# dc26.net
KiCad netlist of a schematic drawn in EAGLE
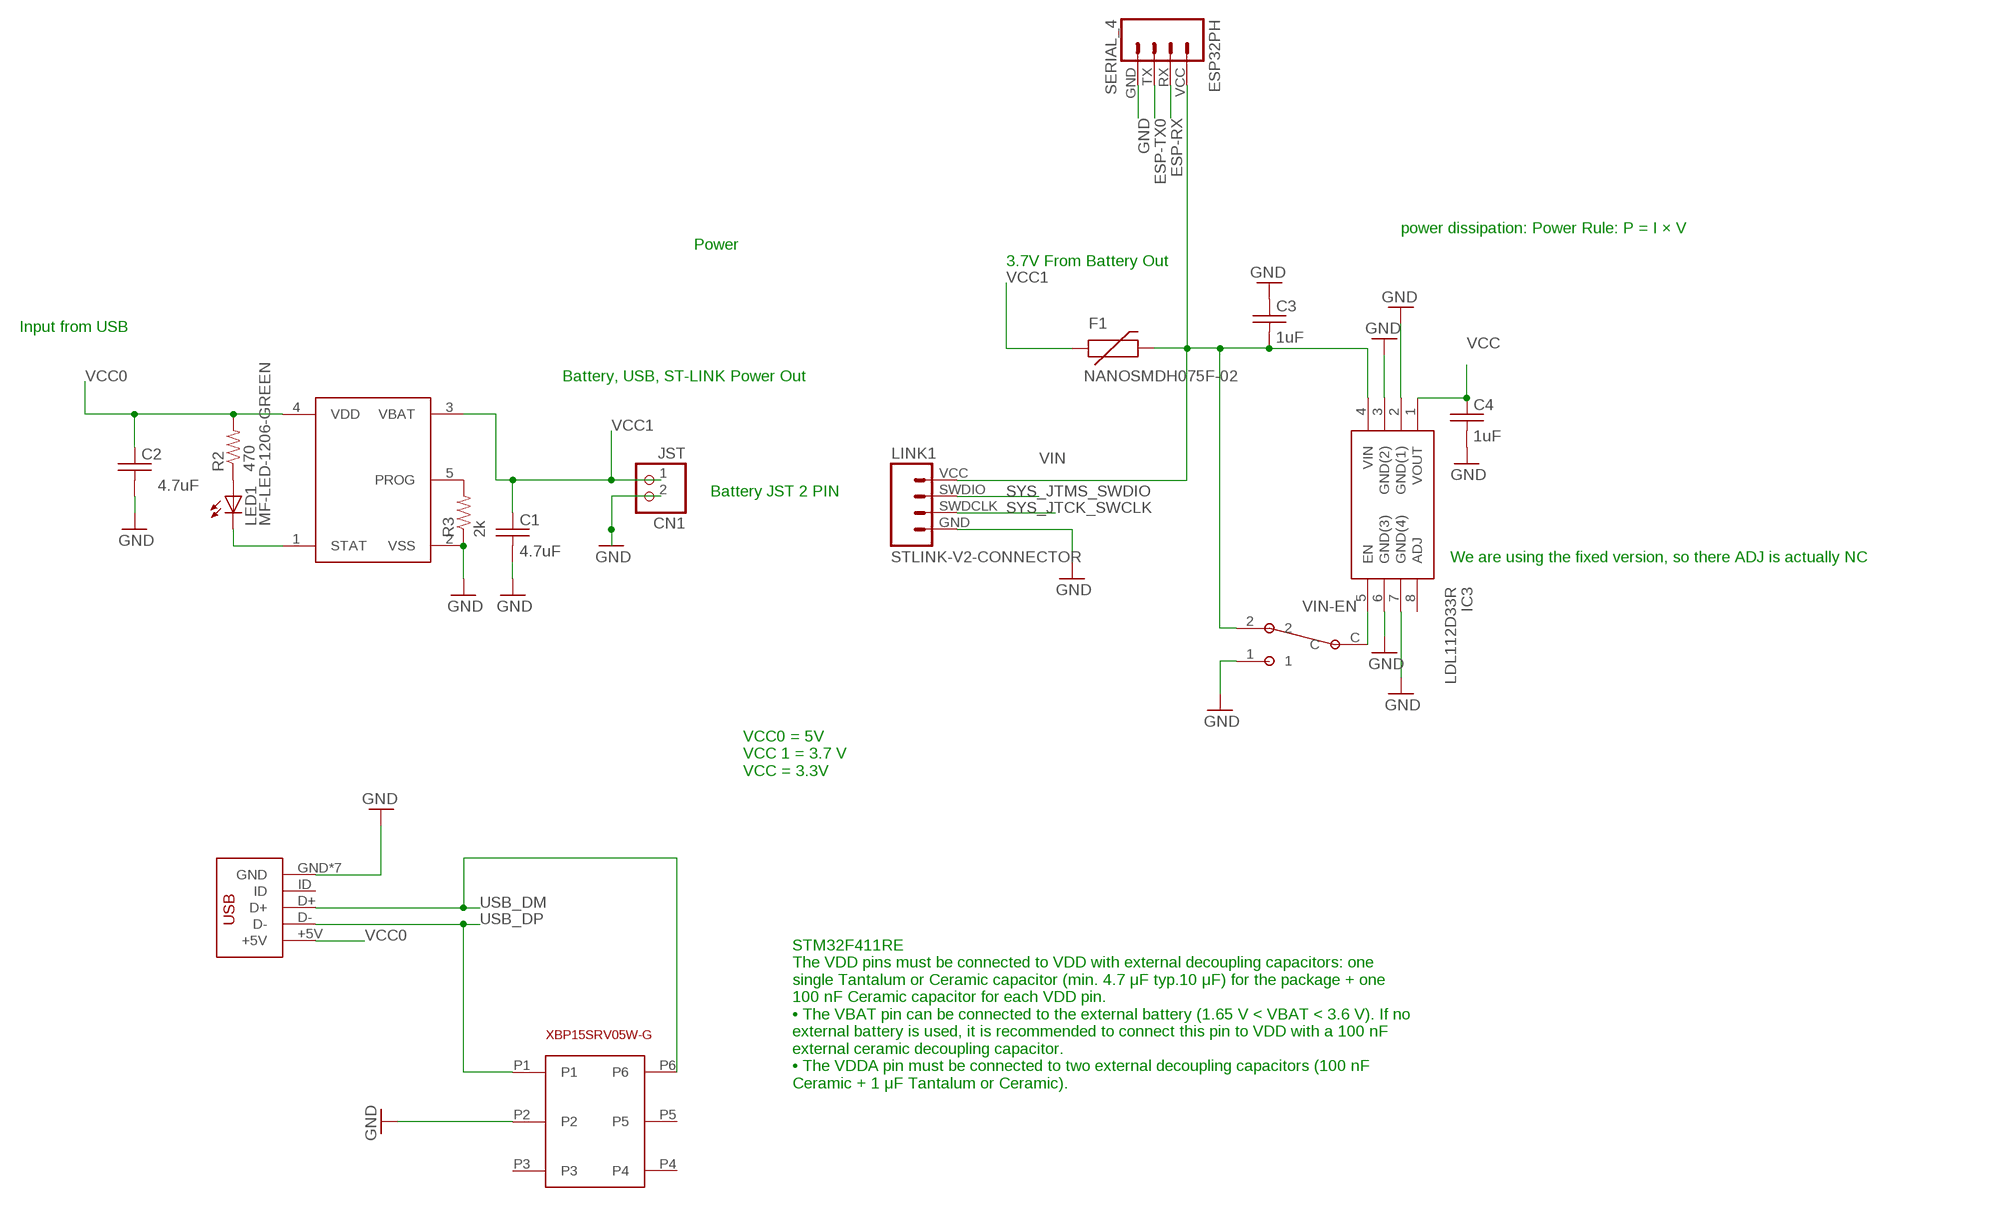
[diagram p0: schematic, sheet 1]
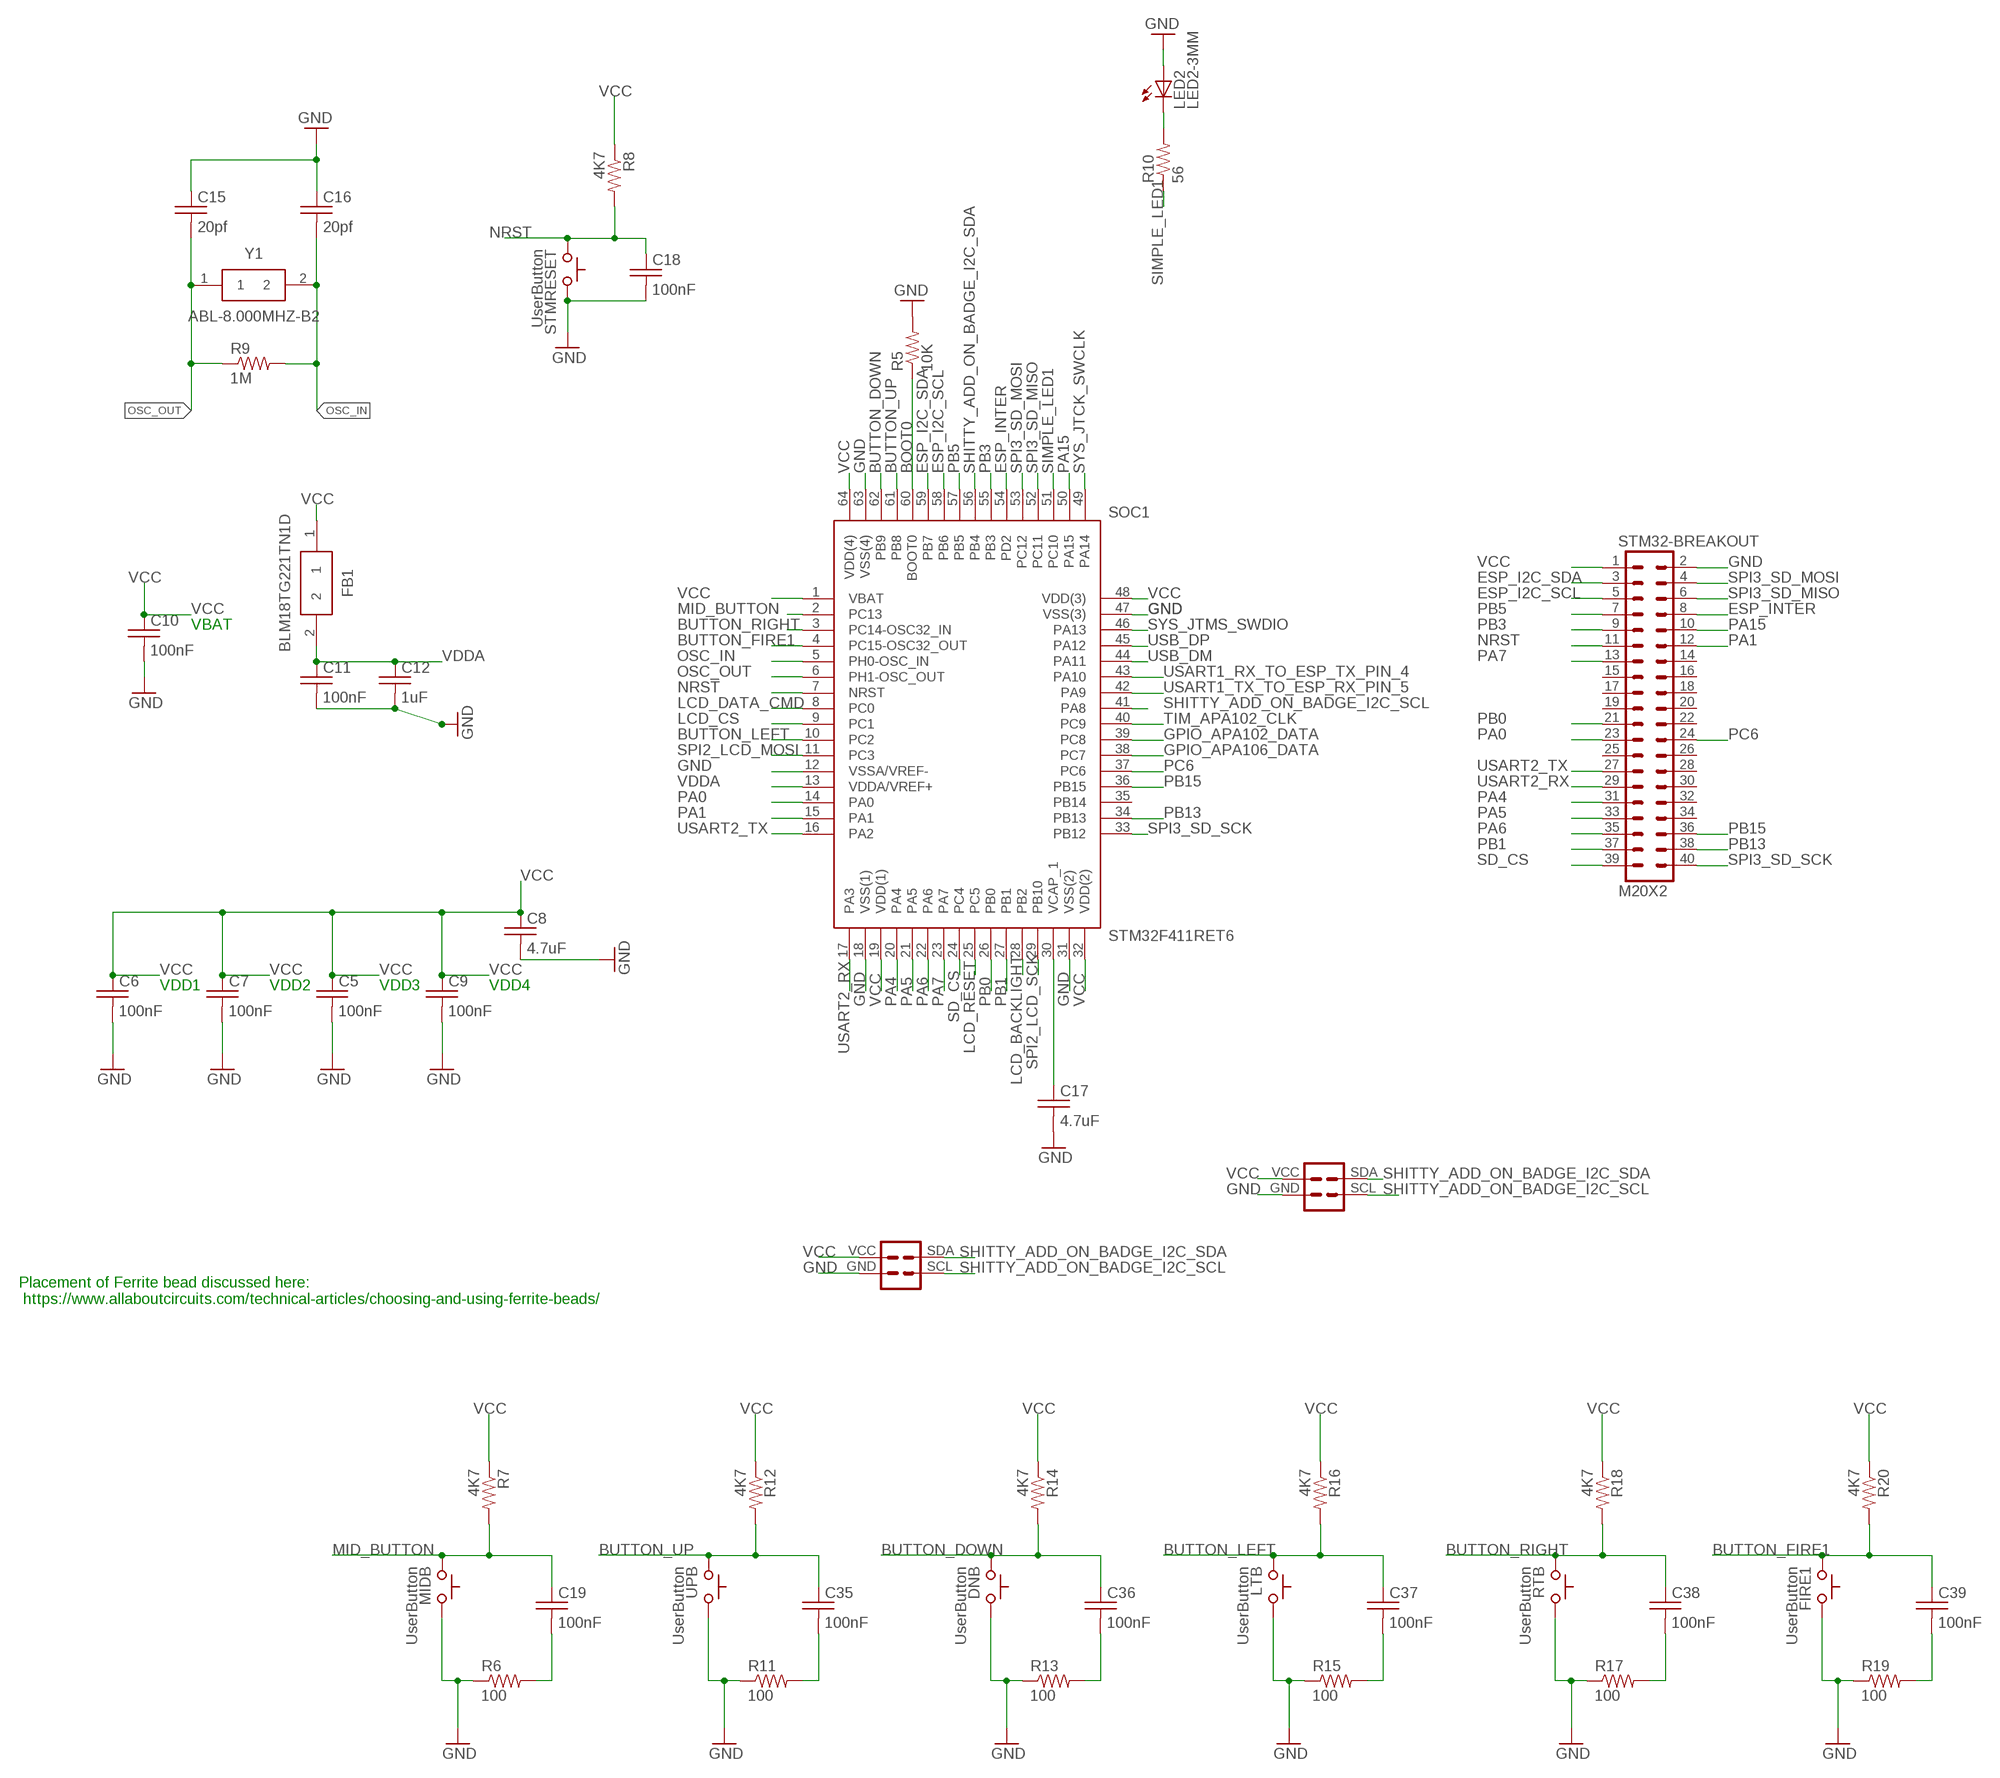
[diagram p1: schematic, sheet 2]
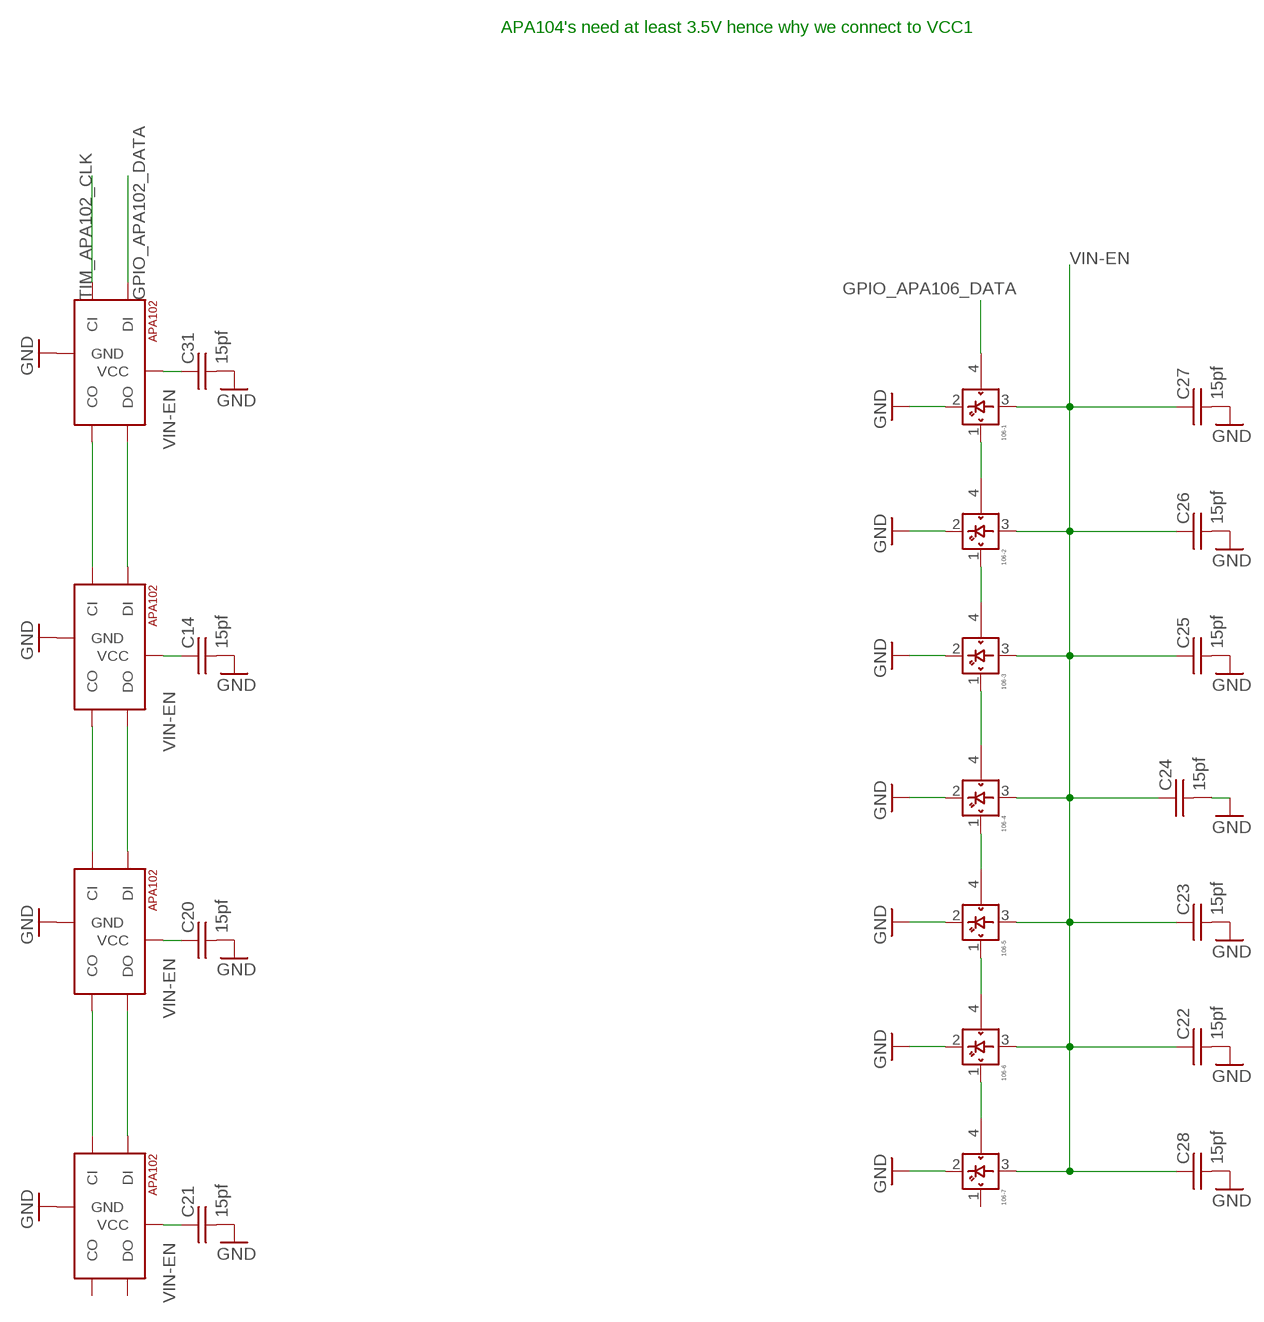
[diagram p2: schematic, sheet 3]
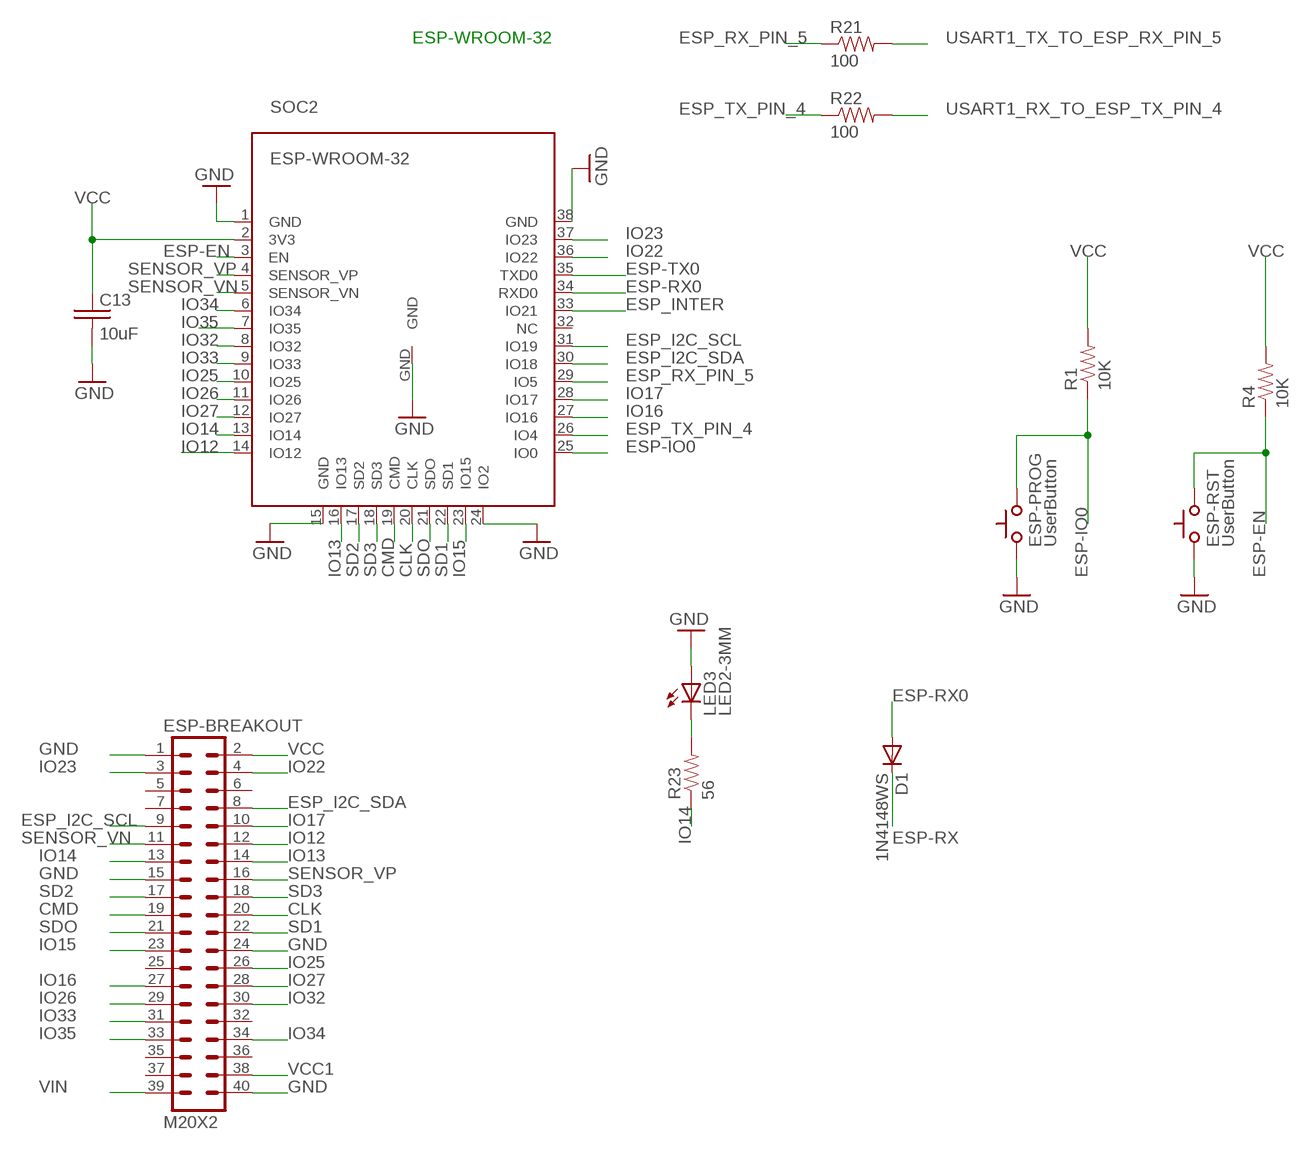
[diagram p3: schematic, sheet 4]
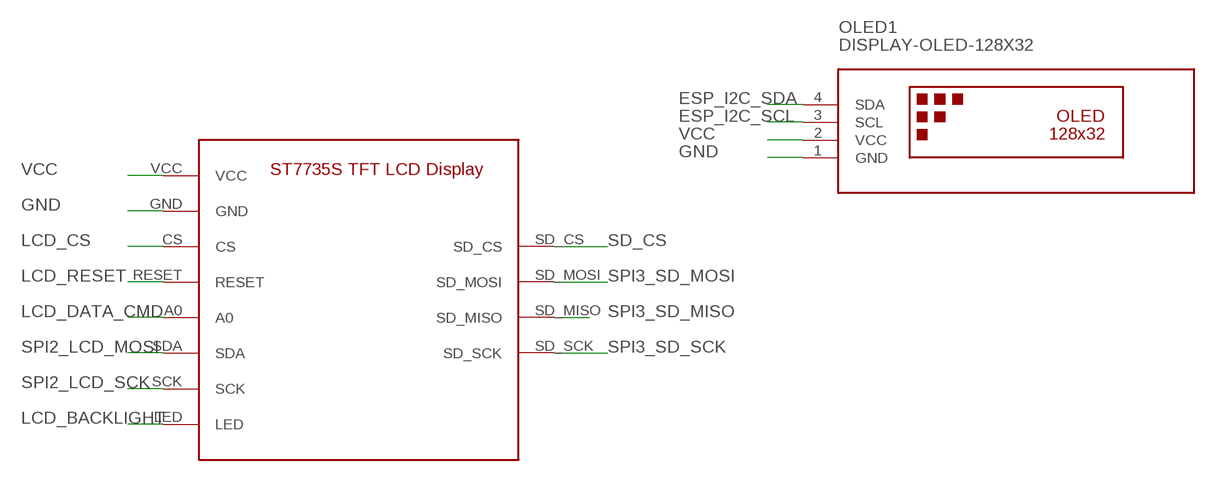
[diagram p4: schematic, sheet 5]
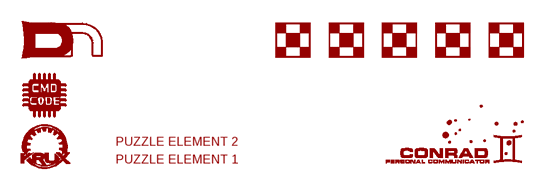
[diagram p5: schematic, sheet 6]
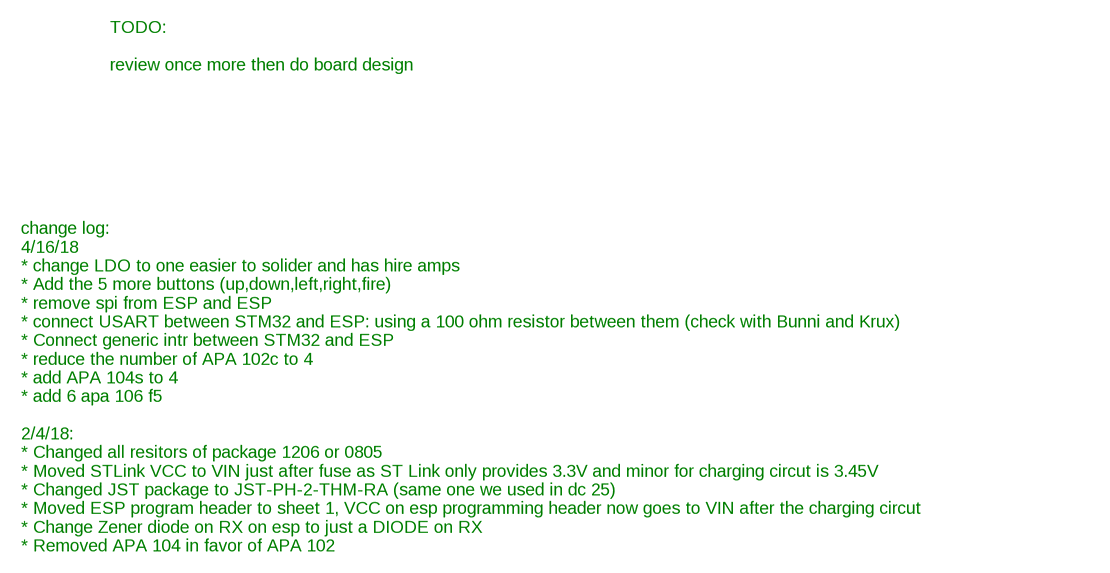
[diagram p6: schematic, sheet 7]

(export (version "E")
  (design (tool "Eeschema 10.0.6"))
  (components
    (comp (ref "C5")
      (value "100nF")
      (footprint "eagle-import:C0805")
      (libsource (lib "eagle-import") (part "C-USC0805"))
    )
    (comp (ref "C6")
      (value "100nF")
      (footprint "eagle-import:C0805")
      (libsource (lib "eagle-import") (part "C-USC0805"))
    )
    (comp (ref "C7")
      (value "100nF")
      (footprint "eagle-import:C0805")
      (libsource (lib "eagle-import") (part "C-USC0805"))
    )
    (comp (ref "C8")
      (value "4.7uF")
      (footprint "eagle-import:C0805")
      (libsource (lib "eagle-import") (part "C-USC0805"))
    )
    (comp (ref "C9")
      (value "100nF")
      (footprint "eagle-import:C0805")
      (libsource (lib "eagle-import") (part "C-USC0805"))
    )
    (comp (ref "C10")
      (value "100nF")
      (footprint "eagle-import:C0805")
      (libsource (lib "eagle-import") (part "C-USC0805"))
    )
    (comp (ref "C11")
      (value "100nF")
      (footprint "eagle-import:C0805")
      (libsource (lib "eagle-import") (part "C-USC0805"))
    )
    (comp (ref "C12")
      (value "1uF")
      (footprint "eagle-import:C0805")
      (libsource (lib "eagle-import") (part "C-USC0805"))
    )
    (comp (ref "C15")
      (value "20pf")
      (footprint "eagle-import:C0805")
      (libsource (lib "eagle-import") (part "C-USC0805"))
    )
    (comp (ref "C16")
      (value "20pf")
      (footprint "eagle-import:C0805")
      (libsource (lib "eagle-import") (part "C-USC0805"))
    )
    (comp (ref "C17")
      (value "4.7uF")
      (footprint "eagle-import:C0805")
      (libsource (lib "eagle-import") (part "C-USC0805"))
    )
    (comp (ref "C18")
      (value "100nF")
      (footprint "eagle-import:C0805")
      (libsource (lib "eagle-import") (part "C-USC0805"))
    )
    (comp (ref "C19")
      (value "100nF")
      (footprint "eagle-import:C0805")
      (libsource (lib "eagle-import") (part "C-USC0805"))
    )
    (comp (ref "C35")
      (value "100nF")
      (footprint "eagle-import:C0805")
      (libsource (lib "eagle-import") (part "C-USC0805"))
    )
    (comp (ref "C36")
      (value "100nF")
      (footprint "eagle-import:C0805")
      (libsource (lib "eagle-import") (part "C-USC0805"))
    )
    (comp (ref "C37")
      (value "100nF")
      (footprint "eagle-import:C0805")
      (libsource (lib "eagle-import") (part "C-USC0805"))
    )
    (comp (ref "C38")
      (value "100nF")
      (footprint "eagle-import:C0805")
      (libsource (lib "eagle-import") (part "C-USC0805"))
    )
    (comp (ref "C39")
      (value "100nF")
      (footprint "eagle-import:C0805")
      (libsource (lib "eagle-import") (part "C-USC0805"))
    )
    (comp (ref "DNB")
      (value "UserButton")
      (footprint "eagle-import:TACTILE-2PIN-NARROW")
      (libsource (lib "eagle-import") (part "SWITCH_TACTILETACTILE-2PIN-NARROW"))
    )
    (comp (ref "FB1")
      (value "BLM18TG221TN1D")
      (footprint "eagle-import:BEADC1608X75N")
      (fields (field (name "RS_PART_NUMBER") "6197526"))
      (libsource (lib "eagle-import") (part "BLM18TG221TN1D"))
    )
    (comp (ref "FIRE1")
      (value "UserButton")
      (footprint "eagle-import:TACTILE-2PIN-NARROW")
      (libsource (lib "eagle-import") (part "SWITCH_TACTILETACTILE-2PIN-NARROW"))
    )
    (comp (ref "J1")
      (value "DC26 Shitty AddOn")
      (footprint "eagle-import:DC26SHITTY_ADDON_CONNECTOR")
      (libsource (lib "eagle-import") (part "DC26_SHITTY_ADDON_CONNECTORPTH"))
    )
    (comp (ref "J2")
      (value "DC26 Shitty AddOn")
      (footprint "eagle-import:DC26SHITTY_ADDON_CONNECTOR")
      (libsource (lib "eagle-import") (part "DC26_SHITTY_ADDON_CONNECTORPTH"))
    )
    (comp (ref "LED2")
      (value "LED2-3MM")
      (footprint "eagle-import:LED3MM")
      (libsource (lib "eagle-import") (part "LED3MM"))
    )
    (comp (ref "LTB")
      (value "UserButton")
      (footprint "eagle-import:TACTILE-2PIN-NARROW")
      (libsource (lib "eagle-import") (part "SWITCH_TACTILETACTILE-2PIN-NARROW"))
    )
    (comp (ref "MIDB")
      (value "UserButton")
      (footprint "eagle-import:TACTILE-2PIN-NARROW")
      (libsource (lib "eagle-import") (part "SWITCH_TACTILETACTILE-2PIN-NARROW"))
    )
    (comp (ref "R5")
      (value "10K")
      (footprint "eagle-import:0805")
      (libsource (lib "eagle-import") (part "RESISTOR0805-RES"))
    )
    (comp (ref "R6")
      (value "100")
      (footprint "eagle-import:0805")
      (libsource (lib "eagle-import") (part "RESISTOR0805-RES"))
    )
    (comp (ref "R7")
      (value "4K7")
      (footprint "eagle-import:0805")
      (libsource (lib "eagle-import") (part "RESISTOR0805-RES"))
    )
    (comp (ref "R8")
      (value "4K7")
      (footprint "eagle-import:0805")
      (libsource (lib "eagle-import") (part "RESISTOR0805-RES"))
    )
    (comp (ref "R9")
      (value "1M")
      (footprint "eagle-import:0805")
      (libsource (lib "eagle-import") (part "RESISTOR0805-RES"))
    )
    (comp (ref "R10")
      (value "56")
      (footprint "eagle-import:0805")
      (libsource (lib "eagle-import") (part "RESISTOR0805-RES"))
    )
    (comp (ref "R11")
      (value "100")
      (footprint "eagle-import:0805")
      (libsource (lib "eagle-import") (part "RESISTOR0805-RES"))
    )
    (comp (ref "R12")
      (value "4K7")
      (footprint "eagle-import:0805")
      (libsource (lib "eagle-import") (part "RESISTOR0805-RES"))
    )
    (comp (ref "R13")
      (value "100")
      (footprint "eagle-import:0805")
      (libsource (lib "eagle-import") (part "RESISTOR0805-RES"))
    )
    (comp (ref "R14")
      (value "4K7")
      (footprint "eagle-import:0805")
      (libsource (lib "eagle-import") (part "RESISTOR0805-RES"))
    )
    (comp (ref "R15")
      (value "100")
      (footprint "eagle-import:0805")
      (libsource (lib "eagle-import") (part "RESISTOR0805-RES"))
    )
    (comp (ref "R16")
      (value "4K7")
      (footprint "eagle-import:0805")
      (libsource (lib "eagle-import") (part "RESISTOR0805-RES"))
    )
    (comp (ref "R17")
      (value "100")
      (footprint "eagle-import:0805")
      (libsource (lib "eagle-import") (part "RESISTOR0805-RES"))
    )
    (comp (ref "R18")
      (value "4K7")
      (footprint "eagle-import:0805")
      (libsource (lib "eagle-import") (part "RESISTOR0805-RES"))
    )
    (comp (ref "R19")
      (value "100")
      (footprint "eagle-import:0805")
      (libsource (lib "eagle-import") (part "RESISTOR0805-RES"))
    )
    (comp (ref "R20")
      (value "4K7")
      (footprint "eagle-import:0805")
      (libsource (lib "eagle-import") (part "RESISTOR0805-RES"))
    )
    (comp (ref "RTB")
      (value "UserButton")
      (footprint "eagle-import:TACTILE-2PIN-NARROW")
      (libsource (lib "eagle-import") (part "SWITCH_TACTILETACTILE-2PIN-NARROW"))
    )
    (comp (ref "SOC1")
      (value "STM32F411RET6")
      (footprint "eagle-import:QFP50P1200X1200X160-64N")
      (fields (field (name "RS_PART_NUMBER") "1106617P"))
      (libsource (lib "eagle-import") (part "STM32F411RET6"))
    )
    (comp (ref "STM32-BREAKOUT")
      (value "M20X2")
      (footprint "eagle-import:2X20")
      (libsource (lib "eagle-import") (part "M20X2"))
    )
    (comp (ref "STMRESET")
      (value "UserButton")
      (footprint "eagle-import:TACTILE-2PIN-NARROW")
      (libsource (lib "eagle-import") (part "SWITCH_TACTILETACTILE-2PIN-NARROW"))
    )
    (comp (ref "UPB")
      (value "UserButton")
      (footprint "eagle-import:TACTILE-2PIN-NARROW")
      (libsource (lib "eagle-import") (part "SWITCH_TACTILETACTILE-2PIN-NARROW"))
    )
    (comp (ref "Y1")
      (value "ABL-8.000MHZ-B2")
      (footprint "eagle-import:HC_49US_(AT49)PTH")
      (libsource (lib "eagle-import") (part "ABL-8.000MHZ-B2"))
    )
    (comp (ref "C13")
      (value "10uF")
      (footprint "eagle-import:C0805")
      (libsource (lib "eagle-import") (part "C-USC0805"))
    )
    (comp (ref "D1")
      (value "1N4148WS")
      (footprint "eagle-import:SOD-323")
      (libsource (lib "eagle-import") (part "DIODESOD"))
    )
    (comp (ref "ESP-BREAKOUT")
      (value "M20X2")
      (footprint "eagle-import:2X20")
      (libsource (lib "eagle-import") (part "M20X2"))
    )
    (comp (ref "ESP-PROG")
      (value "UserButton")
      (footprint "eagle-import:TACTILE-2PIN-NARROW")
      (libsource (lib "eagle-import") (part "SWITCH_TACTILETACTILE-2PIN-NARROW"))
    )
    (comp (ref "ESP-RST")
      (value "UserButton")
      (footprint "eagle-import:TACTILE-2PIN-NARROW")
      (libsource (lib "eagle-import") (part "SWITCH_TACTILETACTILE-2PIN-NARROW"))
    )
    (comp (ref "LED3")
      (value "LED2-3MM")
      (footprint "eagle-import:LED3MM")
      (libsource (lib "eagle-import") (part "LED3MM"))
    )
    (comp (ref "R1")
      (value "10K")
      (footprint "eagle-import:0805")
      (libsource (lib "eagle-import") (part "RESISTOR0805-RES"))
    )
    (comp (ref "R4")
      (value "10K")
      (footprint "eagle-import:0805")
      (libsource (lib "eagle-import") (part "RESISTOR0805-RES"))
    )
    (comp (ref "R21")
      (value "100")
      (footprint "eagle-import:0805")
      (libsource (lib "eagle-import") (part "RESISTOR0805-RES"))
    )
    (comp (ref "R22")
      (value "100")
      (footprint "eagle-import:0805")
      (libsource (lib "eagle-import") (part "RESISTOR0805-RES"))
    )
    (comp (ref "R23")
      (value "56")
      (footprint "eagle-import:0805")
      (libsource (lib "eagle-import") (part "RESISTOR0805-RES"))
    )
    (comp (ref "SOC2")
      (value "ESP-WROOM-32")
      (footprint "eagle-import:ESP-WROOM-32")
      (libsource (lib "eagle-import") (part "ESP-WROOM-32"))
    )
    (comp (ref "C1")
      (value "4.7uF")
      (footprint "eagle-import:C0805")
      (libsource (lib "eagle-import") (part "C-USC0805"))
    )
    (comp (ref "C2")
      (value "4.7uF")
      (footprint "eagle-import:C0805")
      (libsource (lib "eagle-import") (part "C-USC0805"))
    )
    (comp (ref "C3")
      (value "1uF")
      (footprint "eagle-import:C0805")
      (libsource (lib "eagle-import") (part "C-USC0805"))
    )
    (comp (ref "C4")
      (value "1uF")
      (footprint "eagle-import:C0805")
      (libsource (lib "eagle-import") (part "C-USC0805"))
    )
    (comp (ref "CHARGE")
      (value "MCP73831")
      (footprint "eagle-import:SOT23-5")
      (libsource (lib "eagle-import") (part "DS21984E"))
    )
    (comp (ref "CN1")
      (value "JST")
      (footprint "eagle-import:JST-PH-2-THM-RA")
      (libsource (lib "eagle-import") (part "JST_2PIN-THM-RA"))
    )
    (comp (ref "ESP32PH")
      (value "SERIAL_4")
      (footprint "eagle-import:SERIAL_HEADER_4")
      (libsource (lib "eagle-import") (part "SERIAL_4"))
    )
    (comp (ref "F1")
      (value "NANOSMDH075F-02")
      (footprint "eagle-import:PTC-1206")
      (libsource (lib "eagle-import") (part "PTCSMD"))
    )
    (comp (ref "IC3")
      (value "LDL112D33R")
      (footprint "eagle-import:SOIC127P600X175-8N")
      (libsource (lib "eagle-import") (part "LDL112D33R"))
    )
    (comp (ref "LED1")
      (value "MF-LED-1206-GREEN")
      (footprint "eagle-import:LED-1206")
      (libsource (lib "eagle-import") (part "LED1206"))
    )
    (comp (ref "LINK1")
      (value "STLINK-V2-CONNECTOR")
      (footprint "eagle-import:1X04")
      (libsource (lib "eagle-import") (part "STLINK-V2-CONNECTOR"))
    )
    (comp (ref "P1")
      (value "SPDT_SSAJ120100")
      (footprint "eagle-import:SPDT_SSAJ120100")
      (libsource (lib "eagle-import") (part "SWITCH_SPDT"))
    )
    (comp (ref "R2")
      (value "470")
      (footprint "eagle-import:0805")
      (libsource (lib "eagle-import") (part "RESISTOR0805-RES"))
    )
    (comp (ref "R3")
      (value "2k")
      (footprint "eagle-import:0805")
      (libsource (lib "eagle-import") (part "RESISTOR0805-RES"))
    )
    (comp (ref "U$17")
      (value "XBP15SRV05W-G")
      (footprint "eagle-import:SOT-26P-XBP15SRV05W-G")
      (fields (field (name "DIGI_KEY_PART_NUMBER") "893-1422-1-ND"))
      (libsource (lib "eagle-import") (part "XBP15SRV05W-G"))
    )
    (comp (ref "USB")
      (value "DX4R005JJ2DX4R005JJ2")
      (footprint "eagle-import:DX4R005JJ2")
      (libsource (lib "eagle-import") (part "DX4R005JJ2DX4R005JJ2"))
    )
    (comp (ref "102-1")
      (value "APA1025050")
      (footprint "eagle-import:APA102_5050")
      (libsource (lib "eagle-import") (part "APA1025050"))
    )
    (comp (ref "102-2")
      (value "APA1025050")
      (footprint "eagle-import:APA102_5050")
      (libsource (lib "eagle-import") (part "APA1025050"))
    )
    (comp (ref "102-3")
      (value "APA1025050")
      (footprint "eagle-import:APA102_5050")
      (libsource (lib "eagle-import") (part "APA1025050"))
    )
    (comp (ref "102-4")
      (value "APA1025050")
      (footprint "eagle-import:APA102_5050")
      (libsource (lib "eagle-import") (part "APA1025050"))
    )
    (comp (ref "106-1")
      (value "APA-106")
      (footprint "eagle-import:WS2812F5_STRAIGHT")
      (libsource (lib "eagle-import") (part "APA-106"))
    )
    (comp (ref "106-2")
      (value "APA-106")
      (footprint "eagle-import:WS2812F5_STRAIGHT")
      (libsource (lib "eagle-import") (part "APA-106"))
    )
    (comp (ref "106-3")
      (value "APA-106")
      (footprint "eagle-import:WS2812F5_STRAIGHT")
      (libsource (lib "eagle-import") (part "APA-106"))
    )
    (comp (ref "106-4")
      (value "APA-106")
      (footprint "eagle-import:WS2812F5_STRAIGHT")
      (libsource (lib "eagle-import") (part "APA-106"))
    )
    (comp (ref "106-5")
      (value "APA-106")
      (footprint "eagle-import:WS2812F5_STRAIGHT")
      (libsource (lib "eagle-import") (part "APA-106"))
    )
    (comp (ref "106-6")
      (value "APA-106")
      (footprint "eagle-import:WS2812F5_STRAIGHT")
      (libsource (lib "eagle-import") (part "APA-106"))
    )
    (comp (ref "106-7")
      (value "APA-106")
      (footprint "eagle-import:WS2812F5_STRAIGHT")
      (libsource (lib "eagle-import") (part "APA-106"))
    )
    (comp (ref "C14")
      (value "15pf")
      (footprint "eagle-import:C0805")
      (libsource (lib "eagle-import") (part "C-USC0805"))
    )
    (comp (ref "C20")
      (value "15pf")
      (footprint "eagle-import:C0805")
      (libsource (lib "eagle-import") (part "C-USC0805"))
    )
    (comp (ref "C21")
      (value "15pf")
      (footprint "eagle-import:C0805")
      (libsource (lib "eagle-import") (part "C-USC0805"))
    )
    (comp (ref "C22")
      (value "15pf")
      (footprint "eagle-import:C0805")
      (libsource (lib "eagle-import") (part "C-USC0805"))
    )
    (comp (ref "C23")
      (value "15pf")
      (footprint "eagle-import:C0805")
      (libsource (lib "eagle-import") (part "C-USC0805"))
    )
    (comp (ref "C24")
      (value "15pf")
      (footprint "eagle-import:C0805")
      (libsource (lib "eagle-import") (part "C-USC0805"))
    )
    (comp (ref "C25")
      (value "15pf")
      (footprint "eagle-import:C0805")
      (libsource (lib "eagle-import") (part "C-USC0805"))
    )
    (comp (ref "C26")
      (value "15pf")
      (footprint "eagle-import:C0805")
      (libsource (lib "eagle-import") (part "C-USC0805"))
    )
    (comp (ref "C27")
      (value "15pf")
      (footprint "eagle-import:C0805")
      (libsource (lib "eagle-import") (part "C-USC0805"))
    )
    (comp (ref "C28")
      (value "15pf")
      (footprint "eagle-import:C0805")
      (libsource (lib "eagle-import") (part "C-USC0805"))
    )
    (comp (ref "C31")
      (value "15pf")
      (footprint "eagle-import:C0805")
      (libsource (lib "eagle-import") (part "C-USC0805"))
    )
    (comp (ref "LCD1")
      (value "ST7735S_LCD_MODULE")
      (footprint "eagle-import:ST7735S_LCD_DISPLAY")
      (libsource (lib "eagle-import") (part "ST7735S_LCD_MODULE"))
    )
    (comp (ref "OLED1")
      (value "DISPLAY-OLED-128X32")
      (footprint "eagle-import:DISPLAY-OLED-128X32")
      (libsource (lib "eagle-import") (part "DISPLAY-OLED-128X32"))
    )
    (comp (ref "U$1")
      (value "KRUX_LOGO")
      (footprint "eagle-import:KRUX_LOGO")
      (libsource (lib "eagle-import") (part "KRUX_LOGO"))
    )
    (comp (ref "U$2")
      (value "CMD_C0DE_LOGO")
      (footprint "eagle-import:CMD_C0DE_LOGO")
      (libsource (lib "eagle-import") (part "CMD_C0DE_LOGO"))
    )
    (comp (ref "U$3")
      (value "DC26_KRUX_PUZZLE_1")
      (footprint "eagle-import:DN26_KRUX_PUZZLE_1")
      (libsource (lib "eagle-import") (part "DC26_KRUX_PUZZLE_1"))
    )
    (comp (ref "U$4")
      (value "DC26_KRUX_PUZZLE_2")
      (footprint "eagle-import:DN26_KRUX_PUZZLE_2")
      (libsource (lib "eagle-import") (part "DC26_KRUX_PUZZLE_2"))
    )
    (comp (ref "U$5")
      (value "CONRAD_LOGO")
      (footprint "eagle-import:CONRAD_LOGO")
      (libsource (lib "eagle-import") (part "CONRAD_LOGO"))
    )
    (comp (ref "U$6")
      (value "DN_LOGODC26")
      (footprint "eagle-import:DN_LOGO_DC26")
      (libsource (lib "eagle-import") (part "DN_LOGODC26"))
    )
    (comp (ref "U$7")
      (value "FIDUCIAL_DNBOX")
      (footprint "eagle-import:FIDUCIAL_BOX")
      (libsource (lib "eagle-import") (part "FIDUCIAL_DNBOX"))
    )
    (comp (ref "U$8")
      (value "FIDUCIAL_DNBOX")
      (footprint "eagle-import:FIDUCIAL_BOX")
      (libsource (lib "eagle-import") (part "FIDUCIAL_DNBOX"))
    )
    (comp (ref "U$9")
      (value "FIDUCIAL_DNCORNER")
      (footprint "eagle-import:FIDUCIAL_CORNER")
      (libsource (lib "eagle-import") (part "FIDUCIAL_DNCORNER"))
    )
    (comp (ref "U$10")
      (value "FIDUCIAL_DNCORNER")
      (footprint "eagle-import:FIDUCIAL_CORNER")
      (libsource (lib "eagle-import") (part "FIDUCIAL_DNCORNER"))
    )
    (comp (ref "U$11")
      (value "FIDUCIAL_DNCORNER")
      (footprint "eagle-import:FIDUCIAL_CORNER")
      (libsource (lib "eagle-import") (part "FIDUCIAL_DNCORNER"))
    )
  )
  (nets
    (net (code "1") (name "BOOT0") (class "Default")
      (node (ref "R5") (pin "1") (pinfunction "1_1") (pintype "passive"))
      (node (ref "SOC1") (pin "60") (pinfunction "BOOT0_60") (pintype "passive"))
    )
    (net (code "2") (name "BUTTON_DOWN") (class "Default")
      (node (ref "C36") (pin "1") (pinfunction "1_1") (pintype "passive"))
      (node (ref "DNB") (pin "P$2") (pinfunction "C_P$2") (pintype "passive"))
      (node (ref "R14") (pin "2") (pinfunction "2_2") (pintype "passive"))
      (node (ref "SOC1") (pin "62") (pinfunction "PB9_62") (pintype "passive"))
    )
    (net (code "3") (name "BUTTON_FIRE1") (class "Default")
      (node (ref "C39") (pin "1") (pinfunction "1_1") (pintype "passive"))
      (node (ref "FIRE1") (pin "P$2") (pinfunction "C_P$2") (pintype "passive"))
      (node (ref "R20") (pin "2") (pinfunction "2_2") (pintype "passive"))
      (node (ref "SOC1") (pin "4") (pinfunction "PC15-OSC32_OUT_4") (pintype "passive"))
    )
    (net (code "4") (name "BUTTON_LEFT") (class "Default")
      (node (ref "C37") (pin "1") (pinfunction "1_1") (pintype "passive"))
      (node (ref "LTB") (pin "P$2") (pinfunction "C_P$2") (pintype "passive"))
      (node (ref "R16") (pin "2") (pinfunction "2_2") (pintype "passive"))
      (node (ref "SOC1") (pin "10") (pinfunction "PC2_10") (pintype "passive"))
    )
    (net (code "5") (name "BUTTON_RIGHT") (class "Default")
      (node (ref "C38") (pin "1") (pinfunction "1_1") (pintype "passive"))
      (node (ref "R18") (pin "2") (pinfunction "2_2") (pintype "passive"))
      (node (ref "RTB") (pin "P$2") (pinfunction "C_P$2") (pintype "passive"))
      (node (ref "SOC1") (pin "3") (pinfunction "PC14-OSC32_IN_3") (pintype "passive"))
    )
    (net (code "6") (name "BUTTON_UP") (class "Default")
      (node (ref "C35") (pin "1") (pinfunction "1_1") (pintype "passive"))
      (node (ref "R12") (pin "2") (pinfunction "2_2") (pintype "passive"))
      (node (ref "SOC1") (pin "61") (pinfunction "PB8_61") (pintype "passive"))
      (node (ref "UPB") (pin "P$2") (pinfunction "C_P$2") (pintype "passive"))
    )
    (net (code "7") (name "CLK") (class "Default")
      (node (ref "ESP-BREAKOUT") (pin "20") (pinfunction "20_20") (pintype "passive"))
      (node (ref "SOC2") (pin "20") (pinfunction "CLK_20") (pintype "bidirectional"))
    )
    (net (code "8") (name "CMD") (class "Default")
      (node (ref "ESP-BREAKOUT") (pin "19") (pinfunction "19_19") (pintype "passive"))
      (node (ref "SOC2") (pin "19") (pinfunction "CMD_19") (pintype "bidirectional"))
    )
    (net (code "9") (name "ESP-EN") (class "Default")
      (node (ref "ESP-RST") (pin "P$1") (pinfunction "A_P$1") (pintype "passive"))
      (node (ref "R4") (pin "1") (pinfunction "1_1") (pintype "passive"))
      (node (ref "SOC2") (pin "3") (pinfunction "EN_3") (pintype "bidirectional"))
    )
    (net (code "10") (name "ESP-IO0") (class "Default")
      (node (ref "ESP-PROG") (pin "P$1") (pinfunction "A_P$1") (pintype "passive"))
      (node (ref "R1") (pin "1") (pinfunction "1_1") (pintype "passive"))
      (node (ref "SOC2") (pin "25") (pinfunction "IO0_25") (pintype "bidirectional"))
    )
    (net (code "11") (name "ESP-RX") (class "Default")
      (node (ref "D1") (pin "1") (pinfunction "C_1") (pintype "passive"))
      (node (ref "ESP32PH") (pin "RX") (pinfunction "RX_RX") (pintype "bidirectional"))
    )
    (net (code "12") (name "ESP-RX0") (class "Default")
      (node (ref "D1") (pin "2") (pinfunction "A_2") (pintype "passive"))
      (node (ref "SOC2") (pin "34") (pinfunction "RXD0_34") (pintype "bidirectional"))
    )
    (net (code "13") (name "ESP-TX0") (class "Default")
      (node (ref "ESP32PH") (pin "TX") (pinfunction "TX_TX") (pintype "input"))
      (node (ref "SOC2") (pin "35") (pinfunction "TXD0_35") (pintype "bidirectional"))
    )
    (net (code "14") (name "ESP_I2C_SCL") (class "Default")
      (node (ref "ESP-BREAKOUT") (pin "9") (pinfunction "9_9") (pintype "passive"))
      (node (ref "OLED1") (pin "3") (pinfunction "SCL_3") (pintype "bidirectional"))
      (node (ref "SOC1") (pin "58") (pinfunction "PB6_58") (pintype "passive"))
      (node (ref "SOC2") (pin "31") (pinfunction "IO19_31") (pintype "bidirectional"))
      (node (ref "STM32-BREAKOUT") (pin "5") (pinfunction "5_5") (pintype "passive"))
    )
    (net (code "15") (name "ESP_I2C_SDA") (class "Default")
      (node (ref "ESP-BREAKOUT") (pin "8") (pinfunction "8_8") (pintype "passive"))
      (node (ref "OLED1") (pin "4") (pinfunction "SDA_4") (pintype "bidirectional"))
      (node (ref "SOC1") (pin "59") (pinfunction "PB7_59") (pintype "passive"))
      (node (ref "SOC2") (pin "30") (pinfunction "IO18_30") (pintype "bidirectional"))
      (node (ref "STM32-BREAKOUT") (pin "3") (pinfunction "3_3") (pintype "passive"))
    )
    (net (code "16") (name "ESP_INTER") (class "Default")
      (node (ref "SOC1") (pin "54") (pinfunction "PD2_54") (pintype "passive"))
      (node (ref "SOC2") (pin "33") (pinfunction "IO21_33") (pintype "bidirectional"))
      (node (ref "STM32-BREAKOUT") (pin "8") (pinfunction "8_8") (pintype "passive"))
    )
    (net (code "17") (name "ESP_RX_PIN_5") (class "Default")
      (node (ref "R21") (pin "1") (pinfunction "1_1") (pintype "passive"))
      (node (ref "SOC2") (pin "29") (pinfunction "IO5_29") (pintype "bidirectional"))
    )
    (net (code "18") (name "ESP_TX_PIN_4") (class "Default")
      (node (ref "R22") (pin "1") (pinfunction "1_1") (pintype "passive"))
      (node (ref "SOC2") (pin "26") (pinfunction "IO4_26") (pintype "bidirectional"))
    )
    (net (code "19") (name "GND") (class "Default")
      (node (ref "102-1") (pin "6") (pinfunction "GND_6") (pintype "bidirectional"))
      (node (ref "102-2") (pin "6") (pinfunction "GND_6") (pintype "bidirectional"))
      (node (ref "102-3") (pin "6") (pinfunction "GND_6") (pintype "bidirectional"))
      (node (ref "102-4") (pin "6") (pinfunction "GND_6") (pintype "bidirectional"))
      (node (ref "106-1") (pin "2") (pinfunction "GND_2") (pintype "bidirectional"))
      (node (ref "106-2") (pin "2") (pinfunction "GND_2") (pintype "bidirectional"))
      (node (ref "106-3") (pin "2") (pinfunction "GND_2") (pintype "bidirectional"))
      (node (ref "106-4") (pin "2") (pinfunction "GND_2") (pintype "bidirectional"))
      (node (ref "106-5") (pin "2") (pinfunction "GND_2") (pintype "bidirectional"))
      (node (ref "106-6") (pin "2") (pinfunction "GND_2") (pintype "bidirectional"))
      (node (ref "106-7") (pin "2") (pinfunction "GND_2") (pintype "bidirectional"))
      (node (ref "C1") (pin "2") (pinfunction "2_2") (pintype "passive"))
      (node (ref "C10") (pin "2") (pinfunction "2_2") (pintype "passive"))
      (node (ref "C11") (pin "2") (pinfunction "2_2") (pintype "passive"))
      (node (ref "C12") (pin "2") (pinfunction "2_2") (pintype "passive"))
      (node (ref "C13") (pin "2") (pinfunction "2_2") (pintype "passive"))
      (node (ref "C14") (pin "2") (pinfunction "2_2") (pintype "passive"))
      (node (ref "C15") (pin "1") (pinfunction "1_1") (pintype "passive"))
      (node (ref "C16") (pin "1") (pinfunction "1_1") (pintype "passive"))
      (node (ref "C17") (pin "2") (pinfunction "2_2") (pintype "passive"))
      (node (ref "C18") (pin "2") (pinfunction "2_2") (pintype "passive"))
      (node (ref "C2") (pin "2") (pinfunction "2_2") (pintype "passive"))
      (node (ref "C20") (pin "2") (pinfunction "2_2") (pintype "passive"))
      (node (ref "C21") (pin "2") (pinfunction "2_2") (pintype "passive"))
      (node (ref "C22") (pin "2") (pinfunction "2_2") (pintype "passive"))
      (node (ref "C23") (pin "2") (pinfunction "2_2") (pintype "passive"))
      (node (ref "C24") (pin "2") (pinfunction "2_2") (pintype "passive"))
      (node (ref "C25") (pin "2") (pinfunction "2_2") (pintype "passive"))
      (node (ref "C26") (pin "2") (pinfunction "2_2") (pintype "passive"))
      (node (ref "C27") (pin "2") (pinfunction "2_2") (pintype "passive"))
      (node (ref "C28") (pin "2") (pinfunction "2_2") (pintype "passive"))
      (node (ref "C3") (pin "1") (pinfunction "1_1") (pintype "passive"))
      (node (ref "C31") (pin "2") (pinfunction "2_2") (pintype "passive"))
      (node (ref "C4") (pin "2") (pinfunction "2_2") (pintype "passive"))
      (node (ref "C5") (pin "2") (pinfunction "2_2") (pintype "passive"))
      (node (ref "C6") (pin "2") (pinfunction "2_2") (pintype "passive"))
      (node (ref "C7") (pin "2") (pinfunction "2_2") (pintype "passive"))
      (node (ref "C8") (pin "2") (pinfunction "2_2") (pintype "passive"))
      (node (ref "C9") (pin "2") (pinfunction "2_2") (pintype "passive"))
      (node (ref "CHARGE") (pin "2") (pinfunction "VSS_2") (pintype "bidirectional"))
      (node (ref "CN1") (pin "2") (pinfunction "1_2") (pintype "passive"))
      (node (ref "DNB") (pin "P$1") (pinfunction "A_P$1") (pintype "passive"))
      (node (ref "ESP-BREAKOUT") (pin "1") (pinfunction "1_1") (pintype "passive"))
      (node (ref "ESP-BREAKOUT") (pin "15") (pinfunction "15_15") (pintype "passive"))
      (node (ref "ESP-BREAKOUT") (pin "24") (pinfunction "24_24") (pintype "passive"))
      (node (ref "ESP-BREAKOUT") (pin "40") (pinfunction "40_40") (pintype "passive"))
      (node (ref "ESP-PROG") (pin "P$2") (pinfunction "C_P$2") (pintype "passive"))
      (node (ref "ESP-RST") (pin "P$2") (pinfunction "C_P$2") (pintype "passive"))
      (node (ref "ESP32PH") (pin "GND") (pinfunction "GND_GND") (pintype "power_in"))
      (node (ref "FIRE1") (pin "P$1") (pinfunction "A_P$1") (pintype "passive"))
      (node (ref "IC3") (pin "2") (pinfunction "GND(1)_2") (pintype "bidirectional"))
      (node (ref "IC3") (pin "3") (pinfunction "GND(2)_3") (pintype "bidirectional"))
      (node (ref "IC3") (pin "6") (pinfunction "GND(3)_6") (pintype "bidirectional"))
      (node (ref "IC3") (pin "7") (pinfunction "GND(4)_7") (pintype "bidirectional"))
      (node (ref "J1") (pin "GND") (pinfunction "GND_GND") (pintype "power_in"))
      (node (ref "J2") (pin "GND") (pinfunction "GND_GND") (pintype "power_in"))
      (node (ref "LCD1") (pin "GND") (pinfunction "GND_GND") (pintype "bidirectional"))
      (node (ref "LED2") (pin "A") (pinfunction "A_A") (pintype "input"))
      (node (ref "LED3") (pin "A") (pinfunction "A_A") (pintype "input"))
      (node (ref "LINK1") (pin "GND") (pinfunction "GND_GND") (pintype "power_in"))
      (node (ref "LTB") (pin "P$1") (pinfunction "A_P$1") (pintype "passive"))
      (node (ref "MIDB") (pin "P$1") (pinfunction "A_P$1") (pintype "passive"))
      (node (ref "OLED1") (pin "1") (pinfunction "GND_1") (pintype "power_in"))
      (node (ref "P1") (pin "1") (pinfunction "1_1") (pintype "bidirectional"))
      (node (ref "R11") (pin "1") (pinfunction "1_1") (pintype "passive"))
      (node (ref "R13") (pin "1") (pinfunction "1_1") (pintype "passive"))
      (node (ref "R15") (pin "1") (pinfunction "1_1") (pintype "passive"))
      (node (ref "R17") (pin "1") (pinfunction "1_1") (pintype "passive"))
      (node (ref "R19") (pin "1") (pinfunction "1_1") (pintype "passive"))
      (node (ref "R3") (pin "1") (pinfunction "1_1") (pintype "passive"))
      (node (ref "R5") (pin "2") (pinfunction "2_2") (pintype "passive"))
      (node (ref "R6") (pin "1") (pinfunction "1_1") (pintype "passive"))
      (node (ref "RTB") (pin "P$1") (pinfunction "A_P$1") (pintype "passive"))
      (node (ref "SOC1") (pin "12") (pinfunction "VSSA/VREF-_12") (pintype "passive"))
      (node (ref "SOC1") (pin "18") (pinfunction "VSS(1)_18") (pintype "passive"))
      (node (ref "SOC1") (pin "31") (pinfunction "VSS(2)_31") (pintype "passive"))
      (node (ref "SOC1") (pin "47") (pinfunction "VSS(3)_47") (pintype "passive"))
      (node (ref "SOC1") (pin "63") (pinfunction "VSS(4)_63") (pintype "passive"))
      (node (ref "SOC2") (pin "1") (pinfunction "GND_1") (pintype "bidirectional"))
      (node (ref "SOC2") (pin "15") (pinfunction "GND_15") (pintype "bidirectional"))
      (node (ref "SOC2") (pin "24") (pinfunction "IO2_24") (pintype "bidirectional"))
      (node (ref "SOC2") (pin "38") (pinfunction "GND_38") (pintype "bidirectional"))
      (node (ref "SOC2") (pin "GND") (pinfunction "GND_GND") (pintype "bidirectional"))
      (node (ref "STM32-BREAKOUT") (pin "2") (pinfunction "2_2") (pintype "passive"))
      (node (ref "STMRESET") (pin "P$1") (pinfunction "A_P$1") (pintype "passive"))
      (node (ref "U$17") (pin "P2") (pinfunction "P2_P2") (pintype "bidirectional"))
      (node (ref "UPB") (pin "P$1") (pinfunction "A_P$1") (pintype "passive"))
      (node (ref "USB") (pin "GND") (pinfunction "GND_GND") (pintype "bidirectional"))
      (node (ref "USB") (pin "P$10") (pinfunction "GND_P$10") (pintype "bidirectional"))
      (node (ref "USB") (pin "P$11") (pinfunction "GND_P$11") (pintype "bidirectional"))
      (node (ref "USB") (pin "P$6") (pinfunction "GND_P$6") (pintype "bidirectional"))
      (node (ref "USB") (pin "P$7") (pinfunction "GND_P$7") (pintype "bidirectional"))
      (node (ref "USB") (pin "P$8") (pinfunction "GND_P$8") (pintype "bidirectional"))
      (node (ref "USB") (pin "P$9") (pinfunction "GND_P$9") (pintype "bidirectional"))
    )
    (net (code "20") (name "GPIO_APA102_DATA") (class "Default")
      (node (ref "102-1") (pin "4") (pinfunction "DI_4") (pintype "bidirectional"))
      (node (ref "SOC1") (pin "39") (pinfunction "PC8_39") (pintype "passive"))
    )
    (net (code "21") (name "GPIO_APA106_DATA") (class "Default")
      (node (ref "106-1") (pin "4") (pinfunction "DIN_4") (pintype "input"))
      (node (ref "SOC1") (pin "38") (pinfunction "PC7_38") (pintype "passive"))
    )
    (net (code "22") (name "IO12") (class "Default")
      (node (ref "ESP-BREAKOUT") (pin "12") (pinfunction "12_12") (pintype "passive"))
      (node (ref "SOC2") (pin "14") (pinfunction "IO12_14") (pintype "bidirectional"))
    )
    (net (code "23") (name "IO13") (class "Default")
      (node (ref "ESP-BREAKOUT") (pin "14") (pinfunction "14_14") (pintype "passive"))
      (node (ref "SOC2") (pin "16") (pinfunction "IO13_16") (pintype "bidirectional"))
    )
    (net (code "24") (name "IO14") (class "Default")
      (node (ref "ESP-BREAKOUT") (pin "13") (pinfunction "13_13") (pintype "passive"))
      (node (ref "R23") (pin "1") (pinfunction "1_1") (pintype "passive"))
      (node (ref "SOC2") (pin "13") (pinfunction "IO14_13") (pintype "bidirectional"))
    )
    (net (code "25") (name "IO15") (class "Default")
      (node (ref "ESP-BREAKOUT") (pin "23") (pinfunction "23_23") (pintype "passive"))
      (node (ref "SOC2") (pin "23") (pinfunction "IO15_23") (pintype "bidirectional"))
    )
    (net (code "26") (name "IO16") (class "Default")
      (node (ref "ESP-BREAKOUT") (pin "27") (pinfunction "27_27") (pintype "passive"))
      (node (ref "SOC2") (pin "27") (pinfunction "IO16_27") (pintype "bidirectional"))
    )
    (net (code "27") (name "IO17") (class "Default")
      (node (ref "ESP-BREAKOUT") (pin "10") (pinfunction "10_10") (pintype "passive"))
      (node (ref "SOC2") (pin "28") (pinfunction "IO17_28") (pintype "bidirectional"))
    )
    (net (code "28") (name "IO22") (class "Default")
      (node (ref "ESP-BREAKOUT") (pin "4") (pinfunction "4_4") (pintype "passive"))
      (node (ref "SOC2") (pin "36") (pinfunction "IO22_36") (pintype "bidirectional"))
    )
    (net (code "29") (name "IO23") (class "Default")
      (node (ref "ESP-BREAKOUT") (pin "3") (pinfunction "3_3") (pintype "passive"))
      (node (ref "SOC2") (pin "37") (pinfunction "IO23_37") (pintype "bidirectional"))
    )
    (net (code "30") (name "IO25") (class "Default")
      (node (ref "ESP-BREAKOUT") (pin "26") (pinfunction "26_26") (pintype "passive"))
      (node (ref "SOC2") (pin "10") (pinfunction "IO25_10") (pintype "bidirectional"))
    )
    (net (code "31") (name "IO26") (class "Default")
      (node (ref "ESP-BREAKOUT") (pin "29") (pinfunction "29_29") (pintype "passive"))
      (node (ref "SOC2") (pin "11") (pinfunction "IO26_11") (pintype "bidirectional"))
    )
    (net (code "32") (name "IO27") (class "Default")
      (node (ref "ESP-BREAKOUT") (pin "28") (pinfunction "28_28") (pintype "passive"))
      (node (ref "SOC2") (pin "12") (pinfunction "IO27_12") (pintype "bidirectional"))
    )
    (net (code "33") (name "IO32") (class "Default")
      (node (ref "ESP-BREAKOUT") (pin "30") (pinfunction "30_30") (pintype "passive"))
      (node (ref "SOC2") (pin "8") (pinfunction "IO32_8") (pintype "bidirectional"))
    )
    (net (code "34") (name "IO33") (class "Default")
      (node (ref "ESP-BREAKOUT") (pin "31") (pinfunction "31_31") (pintype "passive"))
      (node (ref "SOC2") (pin "9") (pinfunction "IO33_9") (pintype "bidirectional"))
    )
    (net (code "35") (name "IO34") (class "Default")
      (node (ref "ESP-BREAKOUT") (pin "34") (pinfunction "34_34") (pintype "passive"))
      (node (ref "SOC2") (pin "6") (pinfunction "IO34_6") (pintype "bidirectional"))
    )
    (net (code "36") (name "IO35") (class "Default")
      (node (ref "ESP-BREAKOUT") (pin "33") (pinfunction "33_33") (pintype "passive"))
      (node (ref "SOC2") (pin "7") (pinfunction "IO35_7") (pintype "bidirectional"))
    )
    (net (code "37") (name "LCD_BACKLIGHT") (class "Default")
      (node (ref "LCD1") (pin "LED") (pinfunction "LED_LED") (pintype "bidirectional"))
      (node (ref "SOC1") (pin "28") (pinfunction "PB2_28") (pintype "passive"))
    )
    (net (code "38") (name "LCD_CS") (class "Default")
      (node (ref "LCD1") (pin "CS") (pinfunction "CS_CS") (pintype "bidirectional"))
      (node (ref "SOC1") (pin "9") (pinfunction "PC1_9") (pintype "passive"))
    )
    (net (code "39") (name "LCD_DATA_CMD") (class "Default")
      (node (ref "LCD1") (pin "A0") (pinfunction "A0_A0") (pintype "bidirectional"))
      (node (ref "SOC1") (pin "8") (pinfunction "PC0_8") (pintype "passive"))
    )
    (net (code "40") (name "LCD_RESET") (class "Default")
      (node (ref "LCD1") (pin "RESET") (pinfunction "RESET_RESET") (pintype "bidirectional"))
      (node (ref "SOC1") (pin "25") (pinfunction "PC5_25") (pintype "passive"))
    )
    (net (code "41") (name "MID_BUTTON") (class "Default")
      (node (ref "C19") (pin "1") (pinfunction "1_1") (pintype "passive"))
      (node (ref "MIDB") (pin "P$2") (pinfunction "C_P$2") (pintype "passive"))
      (node (ref "R7") (pin "2") (pinfunction "2_2") (pintype "passive"))
      (node (ref "SOC1") (pin "2") (pinfunction "PC13_2") (pintype "passive"))
    )
    (net (code "42") (name "NRST") (class "Default")
      (node (ref "C18") (pin "1") (pinfunction "1_1") (pintype "passive"))
      (node (ref "R8") (pin "2") (pinfunction "2_2") (pintype "passive"))
      (node (ref "SOC1") (pin "7") (pinfunction "NRST_7") (pintype "passive"))
      (node (ref "STM32-BREAKOUT") (pin "11") (pinfunction "11_11") (pintype "passive"))
      (node (ref "STMRESET") (pin "P$2") (pinfunction "C_P$2") (pintype "passive"))
    )
    (net (code "43") (name "Net-(102-1-CO)") (class "Default")
      (node (ref "102-1") (pin "2") (pinfunction "CO_2") (pintype "bidirectional"))
      (node (ref "102-2") (pin "5") (pinfunction "CI_5") (pintype "bidirectional"))
    )
    (net (code "44") (name "Net-(102-1-DO)") (class "Default")
      (node (ref "102-1") (pin "3") (pinfunction "DO_3") (pintype "bidirectional"))
      (node (ref "102-2") (pin "4") (pinfunction "DI_4") (pintype "bidirectional"))
    )
    (net (code "45") (name "Net-(102-2-CO)") (class "Default")
      (node (ref "102-2") (pin "2") (pinfunction "CO_2") (pintype "bidirectional"))
      (node (ref "102-3") (pin "5") (pinfunction "CI_5") (pintype "bidirectional"))
    )
    (net (code "46") (name "Net-(102-2-DO)") (class "Default")
      (node (ref "102-2") (pin "3") (pinfunction "DO_3") (pintype "bidirectional"))
      (node (ref "102-3") (pin "4") (pinfunction "DI_4") (pintype "bidirectional"))
    )
    (net (code "47") (name "Net-(102-3-CO)") (class "Default")
      (node (ref "102-3") (pin "2") (pinfunction "CO_2") (pintype "bidirectional"))
      (node (ref "102-4") (pin "5") (pinfunction "CI_5") (pintype "bidirectional"))
    )
    (net (code "48") (name "Net-(102-3-DO)") (class "Default")
      (node (ref "102-3") (pin "3") (pinfunction "DO_3") (pintype "bidirectional"))
      (node (ref "102-4") (pin "4") (pinfunction "DI_4") (pintype "bidirectional"))
    )
    (net (code "49") (name "Net-(106-1-DOUT)") (class "Default")
      (node (ref "106-1") (pin "1") (pinfunction "DOUT_1") (pintype "output"))
      (node (ref "106-2") (pin "4") (pinfunction "DIN_4") (pintype "input"))
    )
    (net (code "50") (name "Net-(106-2-DOUT)") (class "Default")
      (node (ref "106-2") (pin "1") (pinfunction "DOUT_1") (pintype "output"))
      (node (ref "106-3") (pin "4") (pinfunction "DIN_4") (pintype "input"))
    )
    (net (code "51") (name "Net-(106-3-DOUT)") (class "Default")
      (node (ref "106-3") (pin "1") (pinfunction "DOUT_1") (pintype "output"))
      (node (ref "106-4") (pin "4") (pinfunction "DIN_4") (pintype "input"))
    )
    (net (code "52") (name "Net-(106-4-DOUT)") (class "Default")
      (node (ref "106-4") (pin "1") (pinfunction "DOUT_1") (pintype "output"))
      (node (ref "106-5") (pin "4") (pinfunction "DIN_4") (pintype "input"))
    )
    (net (code "53") (name "Net-(106-5-DOUT)") (class "Default")
      (node (ref "106-5") (pin "1") (pinfunction "DOUT_1") (pintype "output"))
      (node (ref "106-6") (pin "4") (pinfunction "DIN_4") (pintype "input"))
    )
    (net (code "54") (name "Net-(106-6-DOUT)") (class "Default")
      (node (ref "106-6") (pin "1") (pinfunction "DOUT_1") (pintype "output"))
      (node (ref "106-7") (pin "4") (pinfunction "DIN_4") (pintype "input"))
    )
    (net (code "55") (name "Net-(C19-Pad2)") (class "Default")
      (node (ref "C19") (pin "2") (pinfunction "2_2") (pintype "passive"))
      (node (ref "R6") (pin "2") (pinfunction "2_2") (pintype "passive"))
    )
    (net (code "56") (name "Net-(C35-Pad2)") (class "Default")
      (node (ref "C35") (pin "2") (pinfunction "2_2") (pintype "passive"))
      (node (ref "R11") (pin "2") (pinfunction "2_2") (pintype "passive"))
    )
    (net (code "57") (name "Net-(C36-Pad2)") (class "Default")
      (node (ref "C36") (pin "2") (pinfunction "2_2") (pintype "passive"))
      (node (ref "R13") (pin "2") (pinfunction "2_2") (pintype "passive"))
    )
    (net (code "58") (name "Net-(C37-Pad2)") (class "Default")
      (node (ref "C37") (pin "2") (pinfunction "2_2") (pintype "passive"))
      (node (ref "R15") (pin "2") (pinfunction "2_2") (pintype "passive"))
    )
    (net (code "59") (name "Net-(C38-Pad2)") (class "Default")
      (node (ref "C38") (pin "2") (pinfunction "2_2") (pintype "passive"))
      (node (ref "R17") (pin "2") (pinfunction "2_2") (pintype "passive"))
    )
    (net (code "60") (name "Net-(C39-Pad2)") (class "Default")
      (node (ref "C39") (pin "2") (pinfunction "2_2") (pintype "passive"))
      (node (ref "R19") (pin "2") (pinfunction "2_2") (pintype "passive"))
    )
    (net (code "61") (name "Net-(CHARGE-PROG)") (class "Default")
      (node (ref "CHARGE") (pin "5") (pinfunction "PROG_5") (pintype "bidirectional"))
      (node (ref "R3") (pin "2") (pinfunction "2_2") (pintype "passive"))
    )
    (net (code "62") (name "Net-(CHARGE-STAT)") (class "Default")
      (node (ref "CHARGE") (pin "1") (pinfunction "STAT_1") (pintype "bidirectional"))
      (node (ref "LED1") (pin "C") (pinfunction "C_C") (pintype "output"))
    )
    (net (code "63") (name "Net-(LED1-PadA)") (class "Default")
      (node (ref "LED1") (pin "A") (pinfunction "A_A") (pintype "input"))
      (node (ref "R2") (pin "1") (pinfunction "1_1") (pintype "passive"))
    )
    (net (code "64") (name "Net-(LED2-C)") (class "Default")
      (node (ref "LED2") (pin "K") (pinfunction "C_K") (pintype "output"))
      (node (ref "R10") (pin "2") (pinfunction "2_2") (pintype "passive"))
    )
    (net (code "65") (name "Net-(LED3-C)") (class "Default")
      (node (ref "LED3") (pin "K") (pinfunction "C_K") (pintype "output"))
      (node (ref "R23") (pin "2") (pinfunction "2_2") (pintype "passive"))
    )
    (net (code "66") (name "Net-(SOC1-VCAP_1)") (class "Default")
      (node (ref "C17") (pin "1") (pinfunction "1_1") (pintype "passive"))
      (node (ref "SOC1") (pin "30") (pinfunction "VCAP_1_30") (pintype "passive"))
    )
    (net (code "67") (name "OSC_IN") (class "Default")
      (node (ref "C16") (pin "2") (pinfunction "2_2") (pintype "passive"))
      (node (ref "R9") (pin "2") (pinfunction "2_2") (pintype "passive"))
      (node (ref "SOC1") (pin "5") (pinfunction "PH0-OSC_IN_5") (pintype "passive"))
      (node (ref "Y1") (pin "2") (pinfunction "2_2") (pintype "passive"))
    )
    (net (code "68") (name "OSC_OUT") (class "Default")
      (node (ref "C15") (pin "2") (pinfunction "2_2") (pintype "passive"))
      (node (ref "R9") (pin "1") (pinfunction "1_1") (pintype "passive"))
      (node (ref "SOC1") (pin "6") (pinfunction "PH1-OSC_OUT_6") (pintype "passive"))
      (node (ref "Y1") (pin "1") (pinfunction "1_1") (pintype "passive"))
    )
    (net (code "69") (name "PA0") (class "Default")
      (node (ref "SOC1") (pin "14") (pinfunction "PA0_14") (pintype "passive"))
      (node (ref "STM32-BREAKOUT") (pin "23") (pinfunction "23_23") (pintype "passive"))
    )
    (net (code "70") (name "PA1") (class "Default")
      (node (ref "SOC1") (pin "15") (pinfunction "PA1_15") (pintype "passive"))
      (node (ref "STM32-BREAKOUT") (pin "12") (pinfunction "12_12") (pintype "passive"))
    )
    (net (code "71") (name "PA4") (class "Default")
      (node (ref "SOC1") (pin "20") (pinfunction "PA4_20") (pintype "passive"))
      (node (ref "STM32-BREAKOUT") (pin "31") (pinfunction "31_31") (pintype "passive"))
    )
    (net (code "72") (name "PA5") (class "Default")
      (node (ref "SOC1") (pin "21") (pinfunction "PA5_21") (pintype "passive"))
      (node (ref "STM32-BREAKOUT") (pin "33") (pinfunction "33_33") (pintype "passive"))
    )
    (net (code "73") (name "PA6") (class "Default")
      (node (ref "SOC1") (pin "22") (pinfunction "PA6_22") (pintype "passive"))
      (node (ref "STM32-BREAKOUT") (pin "35") (pinfunction "35_35") (pintype "passive"))
    )
    (net (code "74") (name "PA7") (class "Default")
      (node (ref "SOC1") (pin "23") (pinfunction "PA7_23") (pintype "passive"))
      (node (ref "STM32-BREAKOUT") (pin "13") (pinfunction "13_13") (pintype "passive"))
    )
    (net (code "75") (name "PA15") (class "Default")
      (node (ref "SOC1") (pin "50") (pinfunction "PA15_50") (pintype "passive"))
      (node (ref "STM32-BREAKOUT") (pin "10") (pinfunction "10_10") (pintype "passive"))
    )
    (net (code "76") (name "PB0") (class "Default")
      (node (ref "SOC1") (pin "26") (pinfunction "PB0_26") (pintype "passive"))
      (node (ref "STM32-BREAKOUT") (pin "21") (pinfunction "21_21") (pintype "passive"))
    )
    (net (code "77") (name "PB1") (class "Default")
      (node (ref "SOC1") (pin "27") (pinfunction "PB1_27") (pintype "passive"))
      (node (ref "STM32-BREAKOUT") (pin "37") (pinfunction "37_37") (pintype "passive"))
    )
    (net (code "78") (name "PB3") (class "Default")
      (node (ref "SOC1") (pin "55") (pinfunction "PB3_55") (pintype "passive"))
      (node (ref "STM32-BREAKOUT") (pin "9") (pinfunction "9_9") (pintype "passive"))
    )
    (net (code "79") (name "PB5") (class "Default")
      (node (ref "SOC1") (pin "57") (pinfunction "PB5_57") (pintype "passive"))
      (node (ref "STM32-BREAKOUT") (pin "7") (pinfunction "7_7") (pintype "passive"))
    )
    (net (code "80") (name "PB13") (class "Default")
      (node (ref "SOC1") (pin "34") (pinfunction "PB13_34") (pintype "passive"))
      (node (ref "STM32-BREAKOUT") (pin "38") (pinfunction "38_38") (pintype "passive"))
    )
    (net (code "81") (name "PB15") (class "Default")
      (node (ref "SOC1") (pin "36") (pinfunction "PB15_36") (pintype "passive"))
      (node (ref "STM32-BREAKOUT") (pin "36") (pinfunction "36_36") (pintype "passive"))
    )
    (net (code "82") (name "PC6") (class "Default")
      (node (ref "SOC1") (pin "37") (pinfunction "PC6_37") (pintype "passive"))
      (node (ref "STM32-BREAKOUT") (pin "24") (pinfunction "24_24") (pintype "passive"))
    )
    (net (code "83") (name "SD1") (class "Default")
      (node (ref "ESP-BREAKOUT") (pin "22") (pinfunction "22_22") (pintype "passive"))
      (node (ref "SOC2") (pin "22") (pinfunction "SD1_22") (pintype "bidirectional"))
    )
    (net (code "84") (name "SD2") (class "Default")
      (node (ref "ESP-BREAKOUT") (pin "17") (pinfunction "17_17") (pintype "passive"))
      (node (ref "SOC2") (pin "17") (pinfunction "SD2_17") (pintype "bidirectional"))
    )
    (net (code "85") (name "SD3") (class "Default")
      (node (ref "ESP-BREAKOUT") (pin "18") (pinfunction "18_18") (pintype "passive"))
      (node (ref "SOC2") (pin "18") (pinfunction "SD3_18") (pintype "bidirectional"))
    )
    (net (code "86") (name "SDO") (class "Default")
      (node (ref "ESP-BREAKOUT") (pin "21") (pinfunction "21_21") (pintype "passive"))
      (node (ref "SOC2") (pin "21") (pinfunction "SDO_21") (pintype "bidirectional"))
    )
    (net (code "87") (name "SD_CS") (class "Default")
      (node (ref "LCD1") (pin "SD_CS") (pinfunction "SD_CS_SD_CS") (pintype "bidirectional"))
      (node (ref "SOC1") (pin "24") (pinfunction "PC4_24") (pintype "passive"))
      (node (ref "STM32-BREAKOUT") (pin "39") (pinfunction "39_39") (pintype "passive"))
    )
    (net (code "88") (name "SENSOR_VN") (class "Default")
      (node (ref "ESP-BREAKOUT") (pin "11") (pinfunction "11_11") (pintype "passive"))
      (node (ref "SOC2") (pin "5") (pinfunction "SENSOR_VN_5") (pintype "bidirectional"))
    )
    (net (code "89") (name "SENSOR_VP") (class "Default")
      (node (ref "ESP-BREAKOUT") (pin "16") (pinfunction "16_16") (pintype "passive"))
      (node (ref "SOC2") (pin "4") (pinfunction "SENSOR_VP_4") (pintype "bidirectional"))
    )
    (net (code "90") (name "SHITTY_ADD_ON_BADGE_I2C_SCL") (class "Default")
      (node (ref "J1") (pin "SCL") (pinfunction "SCL_SCL") (pintype "bidirectional"))
      (node (ref "J2") (pin "SCL") (pinfunction "SCL_SCL") (pintype "bidirectional"))
      (node (ref "SOC1") (pin "41") (pinfunction "PA8_41") (pintype "passive"))
    )
    (net (code "91") (name "SHITTY_ADD_ON_BADGE_I2C_SDA") (class "Default")
      (node (ref "J1") (pin "SDA") (pinfunction "SDA_SDA") (pintype "bidirectional"))
      (node (ref "J2") (pin "SDA") (pinfunction "SDA_SDA") (pintype "bidirectional"))
      (node (ref "SOC1") (pin "56") (pinfunction "PB4_56") (pintype "passive"))
    )
    (net (code "92") (name "SIMPLE_LED1") (class "Default")
      (node (ref "R10") (pin "1") (pinfunction "1_1") (pintype "passive"))
      (node (ref "SOC1") (pin "51") (pinfunction "PC10_51") (pintype "passive"))
    )
    (net (code "93") (name "SPI2_LCD_MOSI") (class "Default")
      (node (ref "LCD1") (pin "SDA") (pinfunction "SDA_SDA") (pintype "bidirectional"))
      (node (ref "SOC1") (pin "11") (pinfunction "PC3_11") (pintype "passive"))
    )
    (net (code "94") (name "SPI2_LCD_SCK") (class "Default")
      (node (ref "LCD1") (pin "SCK") (pinfunction "SCK_SCK") (pintype "bidirectional"))
      (node (ref "SOC1") (pin "29") (pinfunction "PB10_29") (pintype "passive"))
    )
    (net (code "95") (name "SPI3_SD_MISO") (class "Default")
      (node (ref "LCD1") (pin "SD_MISO") (pinfunction "SD_MISO_SD_MISO") (pintype "bidirectional"))
      (node (ref "SOC1") (pin "52") (pinfunction "PC11_52") (pintype "passive"))
      (node (ref "STM32-BREAKOUT") (pin "6") (pinfunction "6_6") (pintype "passive"))
    )
    (net (code "96") (name "SPI3_SD_MOSI") (class "Default")
      (node (ref "LCD1") (pin "SD_MOSI") (pinfunction "SD_MOSI_SD_MOSI") (pintype "bidirectional"))
      (node (ref "SOC1") (pin "53") (pinfunction "PC12_53") (pintype "passive"))
      (node (ref "STM32-BREAKOUT") (pin "4") (pinfunction "4_4") (pintype "passive"))
    )
    (net (code "97") (name "SPI3_SD_SCK") (class "Default")
      (node (ref "LCD1") (pin "SD_SCK") (pinfunction "SD_SCK_SD_SCK") (pintype "bidirectional"))
      (node (ref "SOC1") (pin "33") (pinfunction "PB12_33") (pintype "passive"))
      (node (ref "STM32-BREAKOUT") (pin "40") (pinfunction "40_40") (pintype "passive"))
    )
    (net (code "98") (name "SYS_JTCK_SWCLK") (class "Default")
      (node (ref "LINK1") (pin "SWDCLK") (pinfunction "SWDCLK_SWDCLK") (pintype "input"))
      (node (ref "SOC1") (pin "49") (pinfunction "PA14_49") (pintype "passive"))
    )
    (net (code "99") (name "SYS_JTMS_SWDIO") (class "Default")
      (node (ref "LINK1") (pin "SWDIO") (pinfunction "SWDIO_SWDIO") (pintype "bidirectional"))
      (node (ref "SOC1") (pin "46") (pinfunction "PA13_46") (pintype "passive"))
    )
    (net (code "100") (name "TIM_APA102_CLK") (class "Default")
      (node (ref "102-1") (pin "5") (pinfunction "CI_5") (pintype "bidirectional"))
      (node (ref "SOC1") (pin "40") (pinfunction "PC9_40") (pintype "passive"))
    )
    (net (code "101") (name "USART1_RX_TO_ESP_TX_PIN_4") (class "Default")
      (node (ref "R22") (pin "2") (pinfunction "2_2") (pintype "passive"))
      (node (ref "SOC1") (pin "43") (pinfunction "PA10_43") (pintype "passive"))
    )
    (net (code "102") (name "USART1_TX_TO_ESP_RX_PIN_5") (class "Default")
      (node (ref "R21") (pin "2") (pinfunction "2_2") (pintype "passive"))
      (node (ref "SOC1") (pin "42") (pinfunction "PA9_42") (pintype "passive"))
    )
    (net (code "103") (name "USART2_RX") (class "Default")
      (node (ref "SOC1") (pin "17") (pinfunction "PA3_17") (pintype "passive"))
      (node (ref "STM32-BREAKOUT") (pin "29") (pinfunction "29_29") (pintype "passive"))
    )
    (net (code "104") (name "USART2_TX") (class "Default")
      (node (ref "SOC1") (pin "16") (pinfunction "PA2_16") (pintype "passive"))
      (node (ref "STM32-BREAKOUT") (pin "27") (pinfunction "27_27") (pintype "passive"))
    )
    (net (code "105") (name "USB_DM") (class "Default")
      (node (ref "SOC1") (pin "44") (pinfunction "PA11_44") (pintype "passive"))
      (node (ref "U$17") (pin "P6") (pinfunction "P6_P6") (pintype "bidirectional"))
      (node (ref "USB") (pin "D+") (pinfunction "D+_D+") (pintype "bidirectional"))
    )
    (net (code "106") (name "USB_DP") (class "Default")
      (node (ref "SOC1") (pin "45") (pinfunction "PA12_45") (pintype "passive"))
      (node (ref "U$17") (pin "P1") (pinfunction "P1_P1") (pintype "bidirectional"))
      (node (ref "USB") (pin "D-") (pinfunction "D-_D-") (pintype "bidirectional"))
    )
    (net (code "107") (name "VCC") (class "Default")
      (node (ref "C10") (pin "1") (pinfunction "1_1") (pintype "passive"))
      (node (ref "C13") (pin "1") (pinfunction "1_1") (pintype "passive"))
      (node (ref "C4") (pin "1") (pinfunction "1_1") (pintype "passive"))
      (node (ref "C5") (pin "1") (pinfunction "1_1") (pintype "passive"))
      (node (ref "C6") (pin "1") (pinfunction "1_1") (pintype "passive"))
      (node (ref "C7") (pin "1") (pinfunction "1_1") (pintype "passive"))
      (node (ref "C8") (pin "1") (pinfunction "1_1") (pintype "passive"))
      (node (ref "C9") (pin "1") (pinfunction "1_1") (pintype "passive"))
      (node (ref "ESP-BREAKOUT") (pin "2") (pinfunction "2_2") (pintype "passive"))
      (node (ref "FB1") (pin "1") (pinfunction "1_1") (pintype "passive"))
      (node (ref "IC3") (pin "1") (pinfunction "VOUT_1") (pintype "bidirectional"))
      (node (ref "J1") (pin "VCC") (pinfunction "VCC_VCC") (pintype "power_in"))
      (node (ref "J2") (pin "VCC") (pinfunction "VCC_VCC") (pintype "power_in"))
      (node (ref "LCD1") (pin "VCC") (pinfunction "VCC_VCC") (pintype "bidirectional"))
      (node (ref "OLED1") (pin "2") (pinfunction "VCC_2") (pintype "power_in"))
      (node (ref "R1") (pin "2") (pinfunction "2_2") (pintype "passive"))
      (node (ref "R12") (pin "1") (pinfunction "1_1") (pintype "passive"))
      (node (ref "R14") (pin "1") (pinfunction "1_1") (pintype "passive"))
      (node (ref "R16") (pin "1") (pinfunction "1_1") (pintype "passive"))
      (node (ref "R18") (pin "1") (pinfunction "1_1") (pintype "passive"))
      (node (ref "R20") (pin "1") (pinfunction "1_1") (pintype "passive"))
      (node (ref "R4") (pin "2") (pinfunction "2_2") (pintype "passive"))
      (node (ref "R7") (pin "1") (pinfunction "1_1") (pintype "passive"))
      (node (ref "R8") (pin "1") (pinfunction "1_1") (pintype "passive"))
      (node (ref "SOC1") (pin "1") (pinfunction "VBAT_1") (pintype "passive"))
      (node (ref "SOC1") (pin "19") (pinfunction "VDD(1)_19") (pintype "passive"))
      (node (ref "SOC1") (pin "32") (pinfunction "VDD(2)_32") (pintype "passive"))
      (node (ref "SOC1") (pin "48") (pinfunction "VDD(3)_48") (pintype "passive"))
      (node (ref "SOC1") (pin "64") (pinfunction "VDD(4)_64") (pintype "passive"))
      (node (ref "SOC2") (pin "2") (pinfunction "3V3_2") (pintype "bidirectional"))
      (node (ref "STM32-BREAKOUT") (pin "1") (pinfunction "1_1") (pintype "passive"))
    )
    (net (code "108") (name "VCC0") (class "Default")
      (node (ref "C2") (pin "1") (pinfunction "1_1") (pintype "passive"))
      (node (ref "CHARGE") (pin "4") (pinfunction "VDD_4") (pintype "bidirectional"))
      (node (ref "R2") (pin "2") (pinfunction "2_2") (pintype "passive"))
      (node (ref "USB") (pin "+5V") (pinfunction "+5V_+5V") (pintype "bidirectional"))
    )
    (net (code "109") (name "VCC1") (class "Default")
      (node (ref "C1") (pin "1") (pinfunction "1_1") (pintype "passive"))
      (node (ref "CHARGE") (pin "3") (pinfunction "VBAT_3") (pintype "bidirectional"))
      (node (ref "CN1") (pin "1") (pinfunction "2_1") (pintype "passive"))
      (node (ref "ESP-BREAKOUT") (pin "38") (pinfunction "38_38") (pintype "passive"))
      (node (ref "F1") (pin "1") (pinfunction "1_1") (pintype "bidirectional"))
    )
    (net (code "110") (name "VDDA") (class "Default")
      (node (ref "C11") (pin "1") (pinfunction "1_1") (pintype "passive"))
      (node (ref "C12") (pin "1") (pinfunction "1_1") (pintype "passive"))
      (node (ref "FB1") (pin "2") (pinfunction "2_2") (pintype "passive"))
      (node (ref "SOC1") (pin "13") (pinfunction "VDDA/VREF+_13") (pintype "passive"))
    )
    (net (code "111") (name "VIN") (class "Default")
      (node (ref "C3") (pin "2") (pinfunction "2_2") (pintype "passive"))
      (node (ref "ESP-BREAKOUT") (pin "39") (pinfunction "39_39") (pintype "passive"))
      (node (ref "ESP32PH") (pin "VCC") (pinfunction "VCC_VCC") (pintype "power_in"))
      (node (ref "F1") (pin "2") (pinfunction "2_2") (pintype "bidirectional"))
      (node (ref "IC3") (pin "4") (pinfunction "VIN_4") (pintype "bidirectional"))
      (node (ref "LINK1") (pin "VCC") (pinfunction "VCC_VCC") (pintype "power_in"))
      (node (ref "P1") (pin "2") (pinfunction "2_2") (pintype "bidirectional"))
    )
    (net (code "112") (name "VIN-EN") (class "Default")
      (node (ref "102-1") (pin "1") (pinfunction "VCC_1") (pintype "bidirectional"))
      (node (ref "102-2") (pin "1") (pinfunction "VCC_1") (pintype "bidirectional"))
      (node (ref "102-3") (pin "1") (pinfunction "VCC_1") (pintype "bidirectional"))
      (node (ref "102-4") (pin "1") (pinfunction "VCC_1") (pintype "bidirectional"))
      (node (ref "106-1") (pin "3") (pinfunction "VDD_3") (pintype "bidirectional"))
      (node (ref "106-2") (pin "3") (pinfunction "VDD_3") (pintype "bidirectional"))
      (node (ref "106-3") (pin "3") (pinfunction "VDD_3") (pintype "bidirectional"))
      (node (ref "106-4") (pin "3") (pinfunction "VDD_3") (pintype "bidirectional"))
      (node (ref "106-5") (pin "3") (pinfunction "VDD_3") (pintype "bidirectional"))
      (node (ref "106-6") (pin "3") (pinfunction "VDD_3") (pintype "bidirectional"))
      (node (ref "106-7") (pin "3") (pinfunction "VDD_3") (pintype "bidirectional"))
      (node (ref "C14") (pin "1") (pinfunction "1_1") (pintype "passive"))
      (node (ref "C20") (pin "1") (pinfunction "1_1") (pintype "passive"))
      (node (ref "C21") (pin "1") (pinfunction "1_1") (pintype "passive"))
      (node (ref "C22") (pin "1") (pinfunction "1_1") (pintype "passive"))
      (node (ref "C23") (pin "1") (pinfunction "1_1") (pintype "passive"))
      (node (ref "C24") (pin "1") (pinfunction "1_1") (pintype "passive"))
      (node (ref "C25") (pin "1") (pinfunction "1_1") (pintype "passive"))
      (node (ref "C26") (pin "1") (pinfunction "1_1") (pintype "passive"))
      (node (ref "C27") (pin "1") (pinfunction "1_1") (pintype "passive"))
      (node (ref "C28") (pin "1") (pinfunction "1_1") (pintype "passive"))
      (node (ref "C31") (pin "1") (pinfunction "1_1") (pintype "passive"))
      (node (ref "IC3") (pin "5") (pinfunction "EN_5") (pintype "bidirectional"))
      (node (ref "P1") (pin "C") (pinfunction "C_C") (pintype "bidirectional"))
    )
    (net (code "113") (name "unconnected-(102-4-CO-Pad2)") (class "Default")
      (node (ref "102-4") (pin "2") (pinfunction "CO_2") (pintype "bidirectional"))
    )
    (net (code "114") (name "unconnected-(102-4-DO-Pad3)") (class "Default")
      (node (ref "102-4") (pin "3") (pinfunction "DO_3") (pintype "bidirectional"))
    )
    (net (code "115") (name "unconnected-(106-7-DOUT-Pad1)") (class "Default")
      (node (ref "106-7") (pin "1") (pinfunction "DOUT_1") (pintype "output"))
    )
    (net (code "116") (name "unconnected-(ESP-BREAKOUT-Pad5)") (class "Default")
      (node (ref "ESP-BREAKOUT") (pin "5") (pinfunction "5_5") (pintype "passive"))
    )
    (net (code "117") (name "unconnected-(ESP-BREAKOUT-Pad6)") (class "Default")
      (node (ref "ESP-BREAKOUT") (pin "6") (pinfunction "6_6") (pintype "passive"))
    )
    (net (code "118") (name "unconnected-(ESP-BREAKOUT-Pad7)") (class "Default")
      (node (ref "ESP-BREAKOUT") (pin "7") (pinfunction "7_7") (pintype "passive"))
    )
    (net (code "119") (name "unconnected-(ESP-BREAKOUT-Pad25)") (class "Default")
      (node (ref "ESP-BREAKOUT") (pin "25") (pinfunction "25_25") (pintype "passive"))
    )
    (net (code "120") (name "unconnected-(ESP-BREAKOUT-Pad32)") (class "Default")
      (node (ref "ESP-BREAKOUT") (pin "32") (pinfunction "32_32") (pintype "passive"))
    )
    (net (code "121") (name "unconnected-(ESP-BREAKOUT-Pad35)") (class "Default")
      (node (ref "ESP-BREAKOUT") (pin "35") (pinfunction "35_35") (pintype "passive"))
    )
    (net (code "122") (name "unconnected-(ESP-BREAKOUT-Pad36)") (class "Default")
      (node (ref "ESP-BREAKOUT") (pin "36") (pinfunction "36_36") (pintype "passive"))
    )
    (net (code "123") (name "unconnected-(ESP-BREAKOUT-Pad37)") (class "Default")
      (node (ref "ESP-BREAKOUT") (pin "37") (pinfunction "37_37") (pintype "passive"))
    )
    (net (code "124") (name "unconnected-(IC3-ADJ-Pad8)") (class "Default")
      (node (ref "IC3") (pin "8") (pinfunction "ADJ_8") (pintype "bidirectional"))
    )
    (net (code "125") (name "unconnected-(SOC1-PB14-Pad35)") (class "Default")
      (node (ref "SOC1") (pin "35") (pinfunction "PB14_35") (pintype "passive"))
    )
    (net (code "126") (name "unconnected-(SOC2-NC-Pad32)") (class "Default")
      (node (ref "SOC2") (pin "32") (pinfunction "NC_32") (pintype "bidirectional"))
    )
    (net (code "127") (name "unconnected-(STM32-BREAKOUT-Pad14)") (class "Default")
      (node (ref "STM32-BREAKOUT") (pin "14") (pinfunction "14_14") (pintype "passive"))
    )
    (net (code "128") (name "unconnected-(STM32-BREAKOUT-Pad15)") (class "Default")
      (node (ref "STM32-BREAKOUT") (pin "15") (pinfunction "15_15") (pintype "passive"))
    )
    (net (code "129") (name "unconnected-(STM32-BREAKOUT-Pad16)") (class "Default")
      (node (ref "STM32-BREAKOUT") (pin "16") (pinfunction "16_16") (pintype "passive"))
    )
    (net (code "130") (name "unconnected-(STM32-BREAKOUT-Pad17)") (class "Default")
      (node (ref "STM32-BREAKOUT") (pin "17") (pinfunction "17_17") (pintype "passive"))
    )
    (net (code "131") (name "unconnected-(STM32-BREAKOUT-Pad18)") (class "Default")
      (node (ref "STM32-BREAKOUT") (pin "18") (pinfunction "18_18") (pintype "passive"))
    )
    (net (code "132") (name "unconnected-(STM32-BREAKOUT-Pad19)") (class "Default")
      (node (ref "STM32-BREAKOUT") (pin "19") (pinfunction "19_19") (pintype "passive"))
    )
    (net (code "133") (name "unconnected-(STM32-BREAKOUT-Pad20)") (class "Default")
      (node (ref "STM32-BREAKOUT") (pin "20") (pinfunction "20_20") (pintype "passive"))
    )
    (net (code "134") (name "unconnected-(STM32-BREAKOUT-Pad22)") (class "Default")
      (node (ref "STM32-BREAKOUT") (pin "22") (pinfunction "22_22") (pintype "passive"))
    )
    (net (code "135") (name "unconnected-(STM32-BREAKOUT-Pad25)") (class "Default")
      (node (ref "STM32-BREAKOUT") (pin "25") (pinfunction "25_25") (pintype "passive"))
    )
    (net (code "136") (name "unconnected-(STM32-BREAKOUT-Pad26)") (class "Default")
      (node (ref "STM32-BREAKOUT") (pin "26") (pinfunction "26_26") (pintype "passive"))
    )
    (net (code "137") (name "unconnected-(STM32-BREAKOUT-Pad28)") (class "Default")
      (node (ref "STM32-BREAKOUT") (pin "28") (pinfunction "28_28") (pintype "passive"))
    )
    (net (code "138") (name "unconnected-(STM32-BREAKOUT-Pad30)") (class "Default")
      (node (ref "STM32-BREAKOUT") (pin "30") (pinfunction "30_30") (pintype "passive"))
    )
    (net (code "139") (name "unconnected-(STM32-BREAKOUT-Pad32)") (class "Default")
      (node (ref "STM32-BREAKOUT") (pin "32") (pinfunction "32_32") (pintype "passive"))
    )
    (net (code "140") (name "unconnected-(STM32-BREAKOUT-Pad34)") (class "Default")
      (node (ref "STM32-BREAKOUT") (pin "34") (pinfunction "34_34") (pintype "passive"))
    )
    (net (code "141") (name "unconnected-(U$17-PadP3)") (class "Default")
      (node (ref "U$17") (pin "P3") (pinfunction "P3_P3") (pintype "bidirectional"))
    )
    (net (code "142") (name "unconnected-(U$17-PadP4)") (class "Default")
      (node (ref "U$17") (pin "P4") (pinfunction "P4_P4") (pintype "bidirectional"))
    )
    (net (code "143") (name "unconnected-(U$17-PadP5)") (class "Default")
      (node (ref "U$17") (pin "P5") (pinfunction "P5_P5") (pintype "bidirectional"))
    )
    (net (code "144") (name "unconnected-(USB-PadID)") (class "Default")
      (node (ref "USB") (pin "ID") (pinfunction "ID_ID") (pintype "bidirectional"))
    )
  )
)
